# 01_fpga.net
KiCad netlist of a schematic drawn in Altium Designer
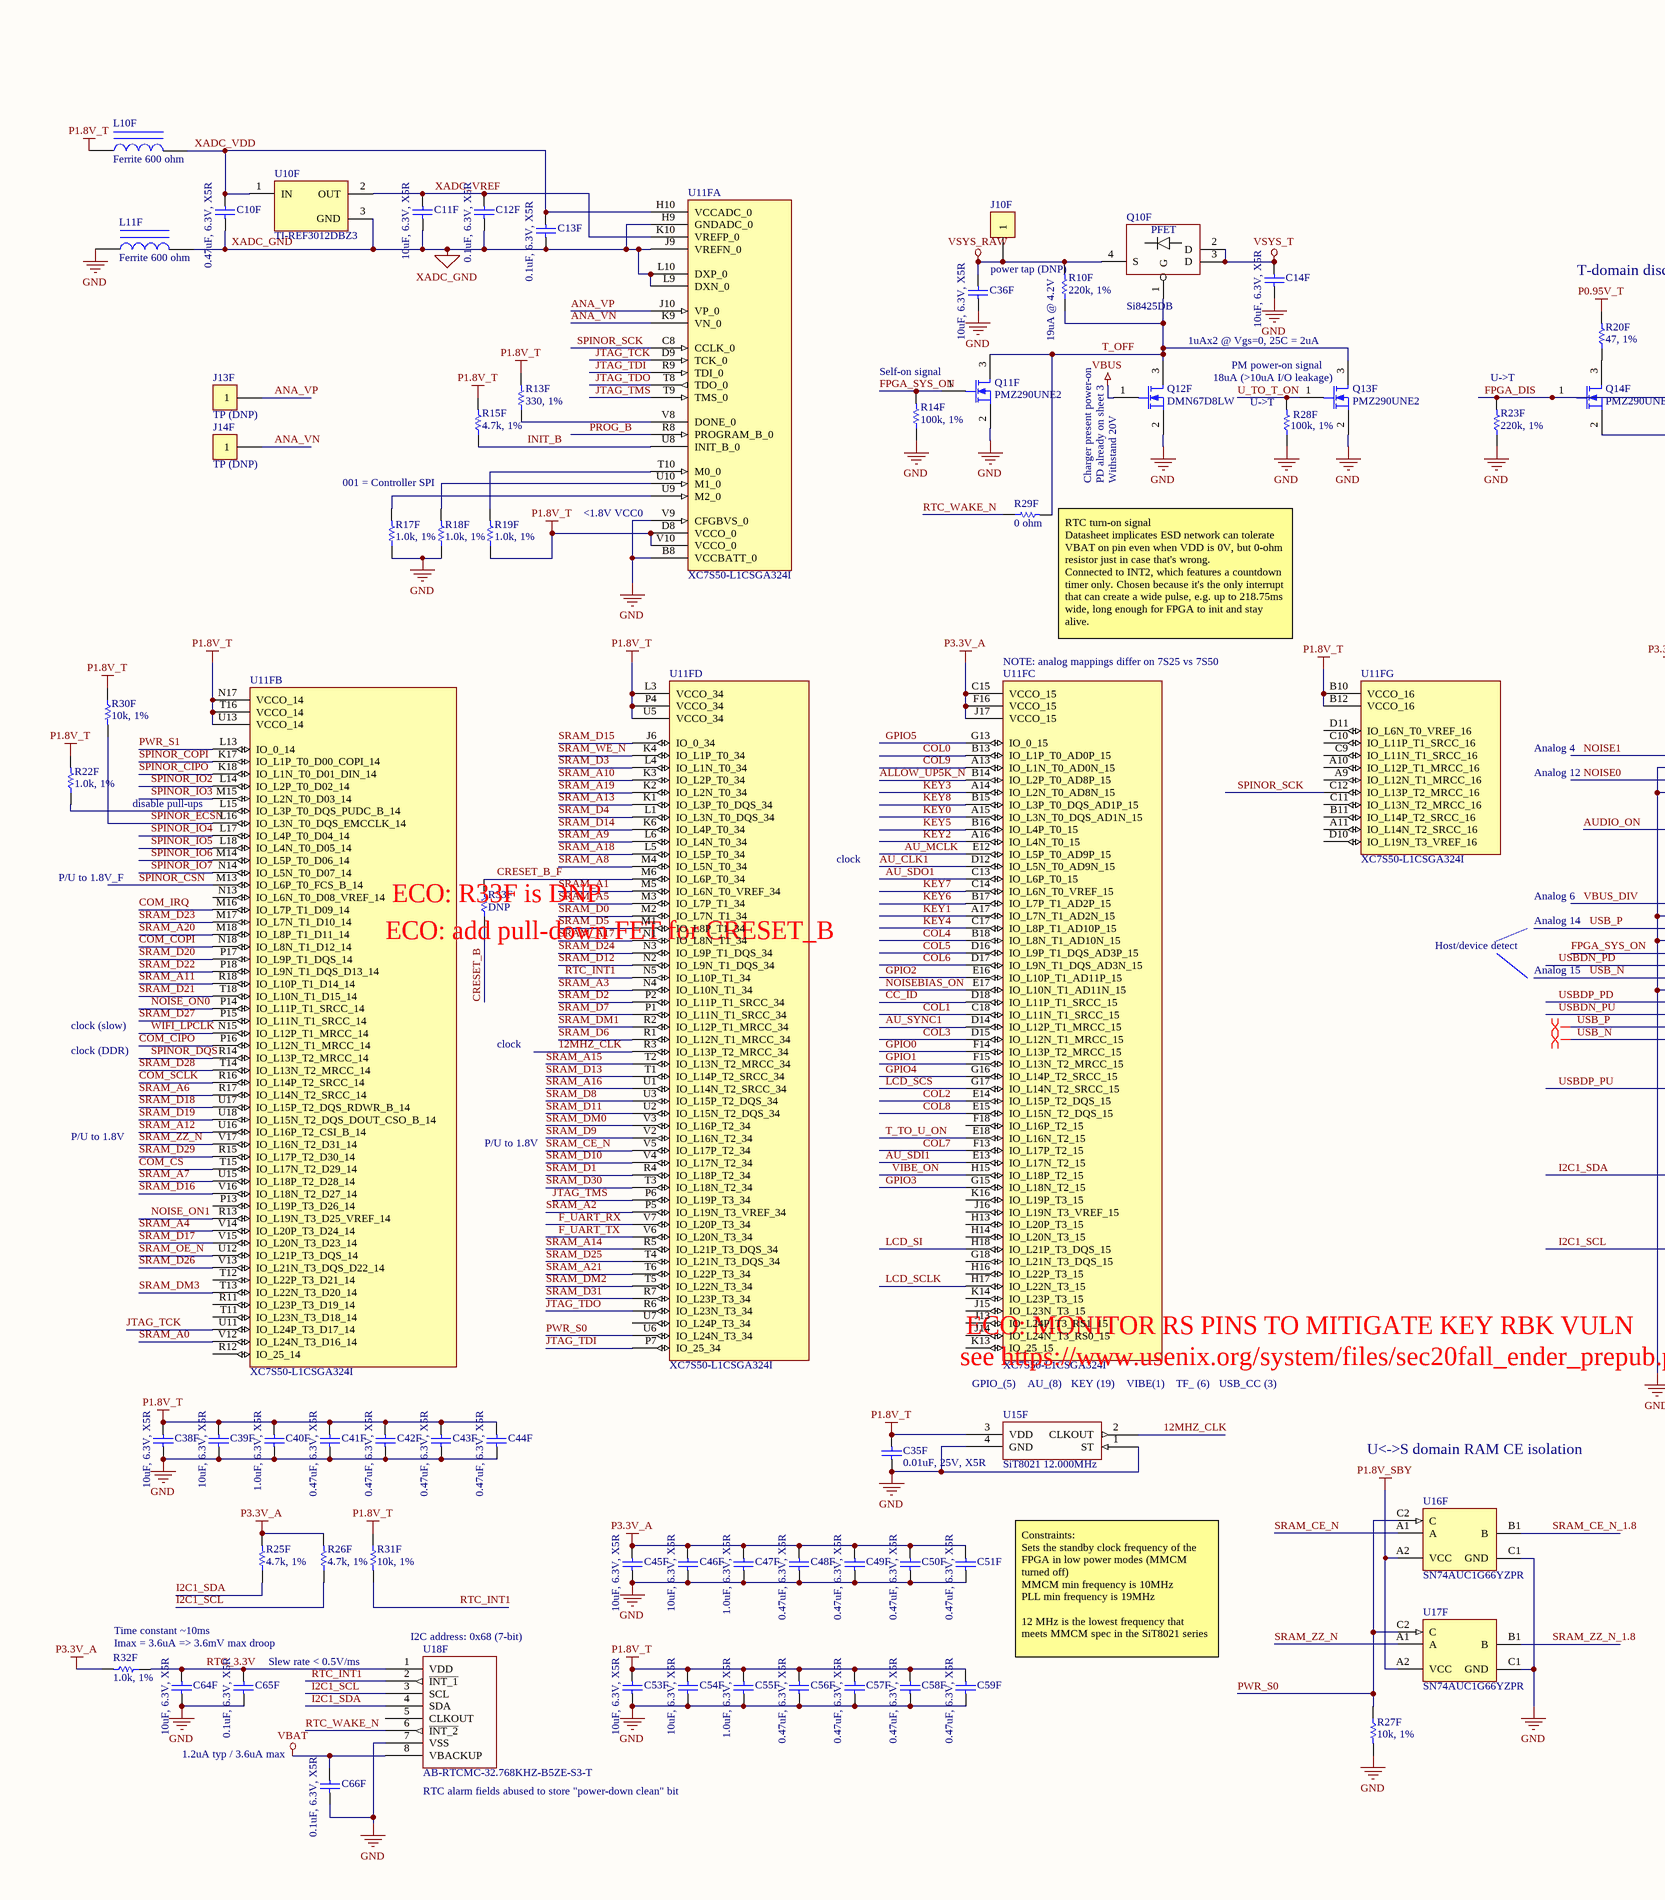
[diagram p0: 01_fpga.SchDoc, left]
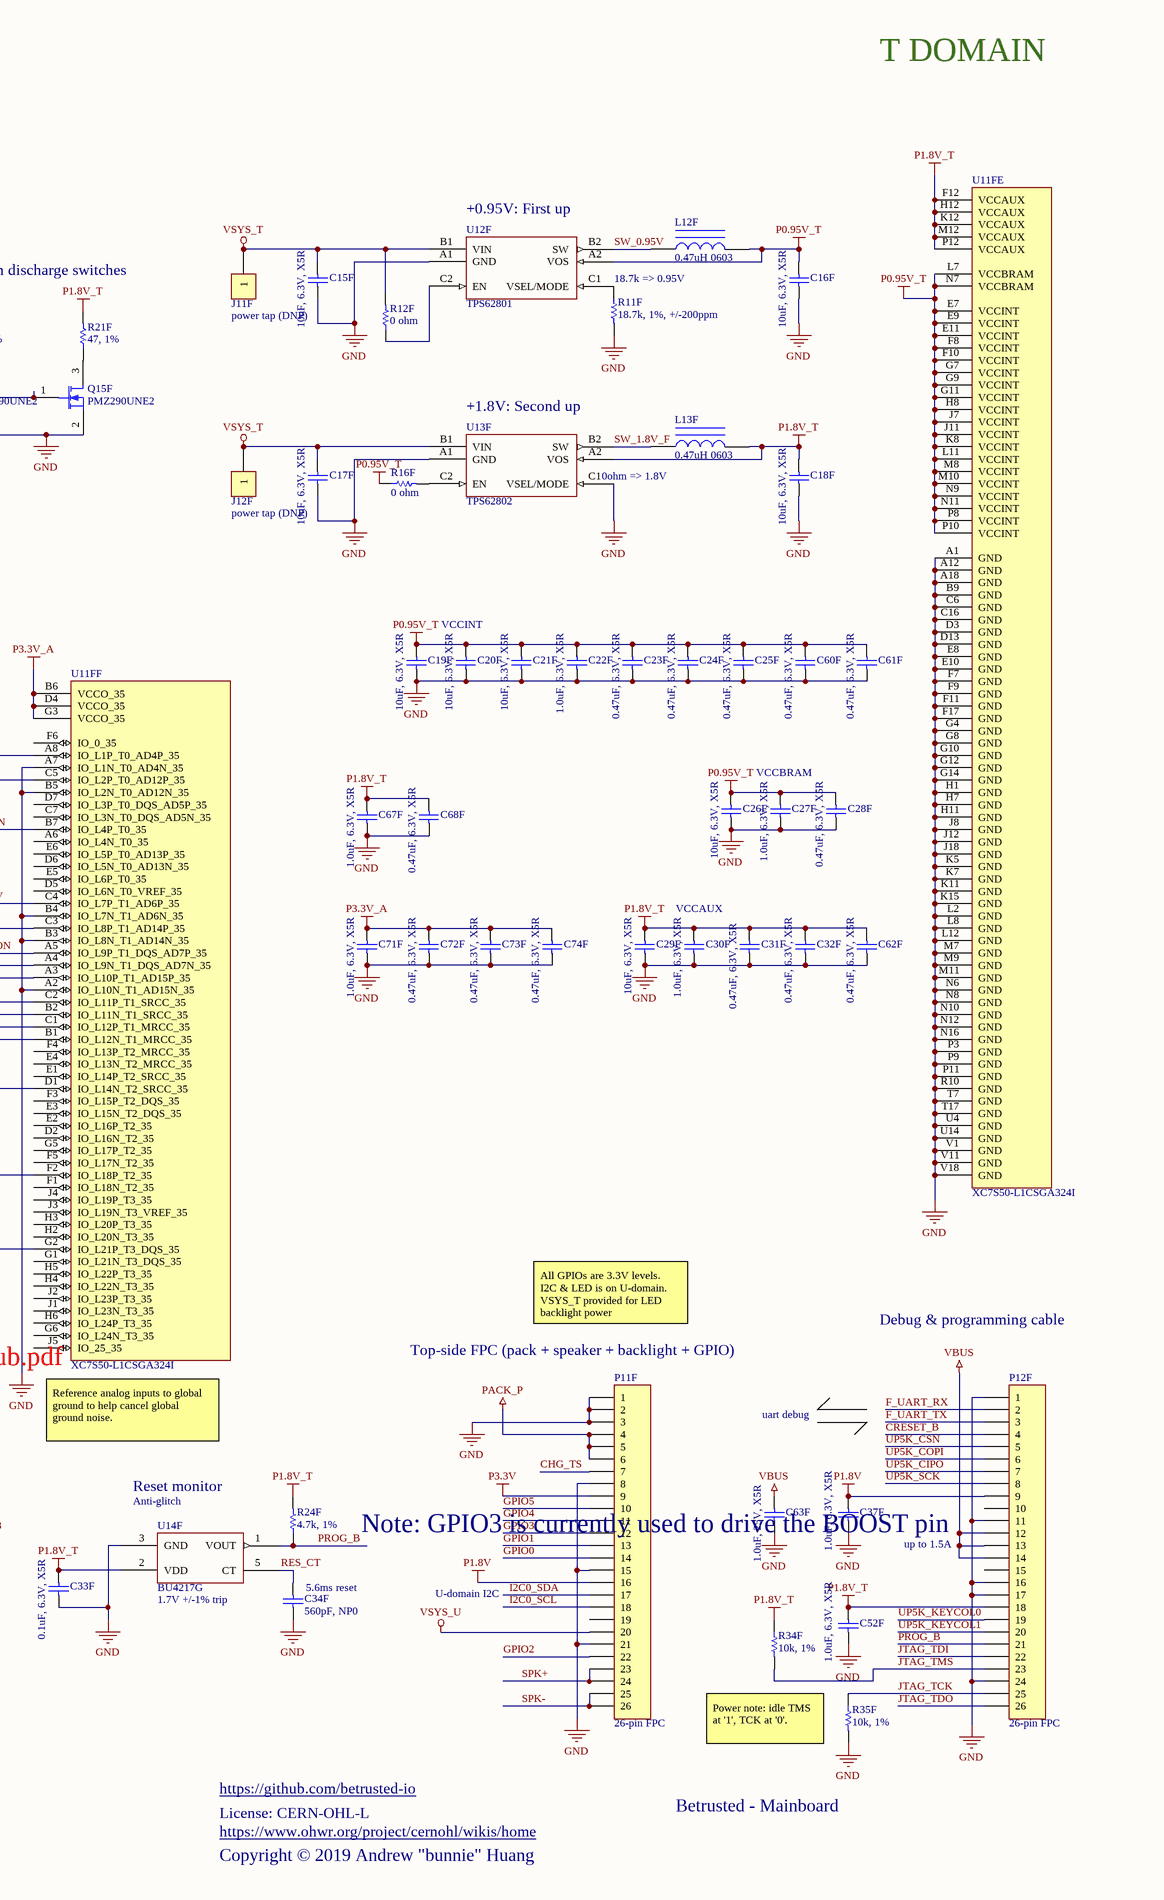
[diagram p1: 01_fpga.SchDoc, right]

(export (version "E")
  (design (tool "Eeschema 10.0.6"))
  (components
    (comp (ref "C10F")
      (value "0.47uF, 6.3V, X5R")
      (footprint "B_CAP0201")
      (description "Capacitor (Semiconductor SIM Model)")
      (fields (field (name "MPN") "CL03A474KQ3NNNH"))
      (libsource (lib "Miscellaneous Devices") (part "Cap Semi"))
    )
    (comp (ref "C11F")
      (value "10uF, 6.3V, X5R")
      (footprint "B_CAP0603")
      (description "Capacitor (Semiconductor SIM Model)")
      (fields (field (name "MPN") "CL10A106MQ8NNNC"))
      (libsource (lib "Miscellaneous Devices") (part "Cap Semi"))
    )
    (comp (ref "C12F")
      (value "0.1uF, 6.3V, X5R")
      (footprint "B_CAP0201")
      (description "Capacitor (Semiconductor SIM Model)")
      (fields (field (name "MPN") "CL03A104KQ3NNNC"))
      (libsource (lib "Miscellaneous Devices") (part "Cap Semi"))
    )
    (comp (ref "C13F")
      (value "0.1uF, 6.3V, X5R")
      (footprint "B_CAP0201")
      (description "Capacitor (Semiconductor SIM Model)")
      (fields (field (name "MPN") "CL03A104KQ3NNNC"))
      (libsource (lib "Miscellaneous Devices") (part "Cap Semi"))
    )
    (comp (ref "C14F")
      (value "10uF, 6.3V, X5R")
      (footprint "B_CAP0603")
      (description "Capacitor (Semiconductor SIM Model)")
      (fields (field (name "MPN") "CL10A106MQ8NNNC"))
      (libsource (lib "Miscellaneous Devices") (part "Cap Semi"))
    )
    (comp (ref "C15F")
      (value "10uF, 6.3V, X5R")
      (footprint "B_CAP0603")
      (description "Capacitor (Semiconductor SIM Model)")
      (fields (field (name "MPN") "CL10A106MQ8NNNC"))
      (libsource (lib "Miscellaneous Devices") (part "Cap Semi"))
    )
    (comp (ref "C16F")
      (value "10uF, 6.3V, X5R")
      (footprint "B_CAP0603")
      (description "Capacitor (Semiconductor SIM Model)")
      (fields (field (name "MPN") "CL10A106MQ8NNNC"))
      (libsource (lib "Miscellaneous Devices") (part "Cap Semi"))
    )
    (comp (ref "C17F")
      (value "10uF, 6.3V, X5R")
      (footprint "B_CAP0603")
      (description "Capacitor (Semiconductor SIM Model)")
      (fields (field (name "MPN") "CL10A106MQ8NNNC"))
      (libsource (lib "Miscellaneous Devices") (part "Cap Semi"))
    )
    (comp (ref "C18F")
      (value "10uF, 6.3V, X5R")
      (footprint "B_CAP0603")
      (description "Capacitor (Semiconductor SIM Model)")
      (fields (field (name "MPN") "CL10A106MQ8NNNC"))
      (libsource (lib "Miscellaneous Devices") (part "Cap Semi"))
    )
    (comp (ref "C19F")
      (value "10uF, 6.3V, X5R")
      (footprint "B_CAP0603")
      (description "Capacitor (Semiconductor SIM Model)")
      (fields (field (name "MPN") "CL10A106MQ8NNNC"))
      (libsource (lib "Miscellaneous Devices") (part "Cap Semi"))
    )
    (comp (ref "C20F")
      (value "10uF, 6.3V, X5R")
      (footprint "B_CAP0603")
      (description "Capacitor (Semiconductor SIM Model)")
      (fields (field (name "MPN") "CL10A106MQ8NNNC"))
      (libsource (lib "Miscellaneous Devices") (part "Cap Semi"))
    )
    (comp (ref "C21F")
      (value "10uF, 6.3V, X5R")
      (footprint "B_CAP0603")
      (description "Capacitor (Semiconductor SIM Model)")
      (fields (field (name "MPN") "CL10A106MQ8NNNC"))
      (libsource (lib "Miscellaneous Devices") (part "Cap Semi"))
    )
    (comp (ref "C22F")
      (value "1.0uF, 6.3V, X5R")
      (footprint "B_CAP0201")
      (description "Capacitor (Semiconductor SIM Model)")
      (fields (field (name "MPN") "GRM033R60J105MEA2D"))
      (libsource (lib "Miscellaneous Devices") (part "Cap Semi"))
    )
    (comp (ref "C23F")
      (value "0.47uF, 6.3V, X5R")
      (footprint "B_CAP0201")
      (description "Capacitor (Semiconductor SIM Model)")
      (fields (field (name "MPN") "CL03A474KQ3NNNH"))
      (libsource (lib "Miscellaneous Devices") (part "Cap Semi"))
    )
    (comp (ref "C24F")
      (value "0.47uF, 6.3V, X5R")
      (footprint "B_CAP0201")
      (description "Capacitor (Semiconductor SIM Model)")
      (fields (field (name "MPN") "CL03A474KQ3NNNH"))
      (libsource (lib "Miscellaneous Devices") (part "Cap Semi"))
    )
    (comp (ref "C25F")
      (value "0.47uF, 6.3V, X5R")
      (footprint "B_CAP0201")
      (description "Capacitor (Semiconductor SIM Model)")
      (fields (field (name "MPN") "CL03A474KQ3NNNH"))
      (libsource (lib "Miscellaneous Devices") (part "Cap Semi"))
    )
    (comp (ref "C26F")
      (value "10uF, 6.3V, X5R")
      (footprint "B_CAP0603")
      (description "Capacitor (Semiconductor SIM Model)")
      (fields (field (name "MPN") "CL10A106MQ8NNNC"))
      (libsource (lib "Miscellaneous Devices") (part "Cap Semi"))
    )
    (comp (ref "C27F")
      (value "1.0uF, 6.3V, X5R")
      (footprint "B_CAP0201")
      (description "Capacitor (Semiconductor SIM Model)")
      (fields (field (name "MPN") "GRM033R60J105MEA2D"))
      (libsource (lib "Miscellaneous Devices") (part "Cap Semi"))
    )
    (comp (ref "C28F")
      (value "0.47uF, 6.3V, X5R")
      (footprint "B_CAP0201")
      (description "Capacitor (Semiconductor SIM Model)")
      (fields (field (name "MPN") "CL03A474KQ3NNNH"))
      (libsource (lib "Miscellaneous Devices") (part "Cap Semi"))
    )
    (comp (ref "C29F")
      (value "10uF, 6.3V, X5R")
      (footprint "B_CAP0603")
      (description "Capacitor (Semiconductor SIM Model)")
      (fields (field (name "MPN") "CL10A106MQ8NNNC"))
      (libsource (lib "Miscellaneous Devices") (part "Cap Semi"))
    )
    (comp (ref "C30F")
      (value "1.0uF, 6.3V, X5R")
      (footprint "B_CAP0201")
      (description "Capacitor (Semiconductor SIM Model)")
      (fields (field (name "MPN") "GRM033R60J105MEA2D"))
      (libsource (lib "Miscellaneous Devices") (part "Cap Semi"))
    )
    (comp (ref "C31F")
      (value "0.47uF, 6.3V, X5R")
      (footprint "B_CAP0201")
      (description "Capacitor (Semiconductor SIM Model)")
      (fields (field (name "MPN") "CL03A474KQ3NNNH"))
      (libsource (lib "Miscellaneous Devices") (part "Cap Semi"))
    )
    (comp (ref "C32F")
      (value "0.47uF, 6.3V, X5R")
      (footprint "B_CAP0201")
      (description "Capacitor (Semiconductor SIM Model)")
      (fields (field (name "MPN") "CL03A474KQ3NNNH"))
      (libsource (lib "Miscellaneous Devices") (part "Cap Semi"))
    )
    (comp (ref "C33F")
      (value "0.1uF, 6.3V, X5R")
      (footprint "B_CAP0201")
      (description "Capacitor (Semiconductor SIM Model)")
      (fields (field (name "MPN") "CL03A104KQ3NNNC"))
      (libsource (lib "Miscellaneous Devices") (part "Cap Semi"))
    )
    (comp (ref "C34F")
      (value "560pF, NP0")
      (footprint "B_RES0201")
      (description "Capacitor (Semiconductor SIM Model)")
      (fields (field (name "MPN") "GRM0335C1E561JA01D"))
      (libsource (lib "Miscellaneous Devices") (part "Cap Semi"))
    )
    (comp (ref "C35F")
      (value "0.01uF, 25V, X5R")
      (footprint "B_RES0201")
      (description "Capacitor (Semiconductor SIM Model)")
      (fields (field (name "MPN") "GRM033R61E103KA12D"))
      (libsource (lib "Miscellaneous Devices") (part "Cap Semi"))
    )
    (comp (ref "C36F")
      (value "10uF, 6.3V, X5R")
      (footprint "B_CAP0603")
      (description "Capacitor (Semiconductor SIM Model)")
      (fields (field (name "MPN") "CL10A106MQ8NNNC"))
      (libsource (lib "Miscellaneous Devices") (part "Cap Semi"))
    )
    (comp (ref "C37F")
      (value "1.0uF, 6.3V, X5R")
      (footprint "B_CAP0201")
      (description "Capacitor (Semiconductor SIM Model)")
      (fields (field (name "MPN") "GRM033R60J105MEA2D"))
      (libsource (lib "Miscellaneous Devices") (part "Cap Semi"))
    )
    (comp (ref "C38F")
      (value "10uF, 6.3V, X5R")
      (footprint "B_CAP0603")
      (description "Capacitor (Semiconductor SIM Model)")
      (fields (field (name "MPN") "CL10A106MQ8NNNC"))
      (libsource (lib "Miscellaneous Devices") (part "Cap Semi"))
    )
    (comp (ref "C39F")
      (value "10uF, 6.3V, X5R")
      (footprint "B_CAP0603")
      (description "Capacitor (Semiconductor SIM Model)")
      (fields (field (name "MPN") "CL10A106MQ8NNNC"))
      (libsource (lib "Miscellaneous Devices") (part "Cap Semi"))
    )
    (comp (ref "C40F")
      (value "1.0uF, 6.3V, X5R")
      (footprint "B_CAP0201")
      (description "Capacitor (Semiconductor SIM Model)")
      (fields (field (name "MPN") "GRM033R60J105MEA2D"))
      (libsource (lib "Miscellaneous Devices") (part "Cap Semi"))
    )
    (comp (ref "C41F")
      (value "0.47uF, 6.3V, X5R")
      (footprint "B_CAP0201")
      (description "Capacitor (Semiconductor SIM Model)")
      (fields (field (name "MPN") "CL03A474KQ3NNNH"))
      (libsource (lib "Miscellaneous Devices") (part "Cap Semi"))
    )
    (comp (ref "C42F")
      (value "0.47uF, 6.3V, X5R")
      (footprint "B_CAP0201")
      (description "Capacitor (Semiconductor SIM Model)")
      (fields (field (name "MPN") "CL03A474KQ3NNNH"))
      (libsource (lib "Miscellaneous Devices") (part "Cap Semi"))
    )
    (comp (ref "C43F")
      (value "0.47uF, 6.3V, X5R")
      (footprint "B_CAP0201")
      (description "Capacitor (Semiconductor SIM Model)")
      (fields (field (name "MPN") "CL03A474KQ3NNNH"))
      (libsource (lib "Miscellaneous Devices") (part "Cap Semi"))
    )
    (comp (ref "C44F")
      (value "0.47uF, 6.3V, X5R")
      (footprint "B_CAP0201")
      (description "Capacitor (Semiconductor SIM Model)")
      (fields (field (name "MPN") "CL03A474KQ3NNNH"))
      (libsource (lib "Miscellaneous Devices") (part "Cap Semi"))
    )
    (comp (ref "C45F")
      (value "10uF, 6.3V, X5R")
      (footprint "B_CAP0603")
      (description "Capacitor (Semiconductor SIM Model)")
      (fields (field (name "MPN") "CL10A106MQ8NNNC"))
      (libsource (lib "Miscellaneous Devices") (part "Cap Semi"))
    )
    (comp (ref "C46F")
      (value "10uF, 6.3V, X5R")
      (footprint "B_CAP0603")
      (description "Capacitor (Semiconductor SIM Model)")
      (fields (field (name "MPN") "CL10A106MQ8NNNC"))
      (libsource (lib "Miscellaneous Devices") (part "Cap Semi"))
    )
    (comp (ref "C47F")
      (value "1.0uF, 6.3V, X5R")
      (footprint "B_CAP0201")
      (description "Capacitor (Semiconductor SIM Model)")
      (fields (field (name "MPN") "GRM033R60J105MEA2D"))
      (libsource (lib "Miscellaneous Devices") (part "Cap Semi"))
    )
    (comp (ref "C48F")
      (value "0.47uF, 6.3V, X5R")
      (footprint "B_CAP0201")
      (description "Capacitor (Semiconductor SIM Model)")
      (fields (field (name "MPN") "CL03A474KQ3NNNH"))
      (libsource (lib "Miscellaneous Devices") (part "Cap Semi"))
    )
    (comp (ref "C49F")
      (value "0.47uF, 6.3V, X5R")
      (footprint "B_CAP0201")
      (description "Capacitor (Semiconductor SIM Model)")
      (fields (field (name "MPN") "CL03A474KQ3NNNH"))
      (libsource (lib "Miscellaneous Devices") (part "Cap Semi"))
    )
    (comp (ref "C50F")
      (value "0.47uF, 6.3V, X5R")
      (footprint "B_CAP0201")
      (description "Capacitor (Semiconductor SIM Model)")
      (fields (field (name "MPN") "CL03A474KQ3NNNH"))
      (libsource (lib "Miscellaneous Devices") (part "Cap Semi"))
    )
    (comp (ref "C51F")
      (value "0.47uF, 6.3V, X5R")
      (footprint "B_CAP0201")
      (description "Capacitor (Semiconductor SIM Model)")
      (fields (field (name "MPN") "CL03A474KQ3NNNH"))
      (libsource (lib "Miscellaneous Devices") (part "Cap Semi"))
    )
    (comp (ref "C52F")
      (value "1.0uF, 6.3V, X5R")
      (footprint "B_CAP0201")
      (description "Capacitor (Semiconductor SIM Model)")
      (fields (field (name "MPN") "GRM033R60J105MEA2D"))
      (libsource (lib "Miscellaneous Devices") (part "Cap Semi"))
    )
    (comp (ref "C53F")
      (value "10uF, 6.3V, X5R")
      (footprint "B_CAP0603")
      (description "Capacitor (Semiconductor SIM Model)")
      (fields (field (name "MPN") "CL10A106MQ8NNNC"))
      (libsource (lib "Miscellaneous Devices") (part "Cap Semi"))
    )
    (comp (ref "C54F")
      (value "10uF, 6.3V, X5R")
      (footprint "B_CAP0603")
      (description "Capacitor (Semiconductor SIM Model)")
      (fields (field (name "MPN") "CL10A106MQ8NNNC"))
      (libsource (lib "Miscellaneous Devices") (part "Cap Semi"))
    )
    (comp (ref "C55F")
      (value "1.0uF, 6.3V, X5R")
      (footprint "B_CAP0201")
      (description "Capacitor (Semiconductor SIM Model)")
      (fields (field (name "MPN") "GRM033R60J105MEA2D"))
      (libsource (lib "Miscellaneous Devices") (part "Cap Semi"))
    )
    (comp (ref "C56F")
      (value "0.47uF, 6.3V, X5R")
      (footprint "B_CAP0201")
      (description "Capacitor (Semiconductor SIM Model)")
      (fields (field (name "MPN") "CL03A474KQ3NNNH"))
      (libsource (lib "Miscellaneous Devices") (part "Cap Semi"))
    )
    (comp (ref "C57F")
      (value "0.47uF, 6.3V, X5R")
      (footprint "B_CAP0201")
      (description "Capacitor (Semiconductor SIM Model)")
      (fields (field (name "MPN") "CL03A474KQ3NNNH"))
      (libsource (lib "Miscellaneous Devices") (part "Cap Semi"))
    )
    (comp (ref "C58F")
      (value "0.47uF, 6.3V, X5R")
      (footprint "B_CAP0201")
      (description "Capacitor (Semiconductor SIM Model)")
      (fields (field (name "MPN") "CL03A474KQ3NNNH"))
      (libsource (lib "Miscellaneous Devices") (part "Cap Semi"))
    )
    (comp (ref "C59F")
      (value "0.47uF, 6.3V, X5R")
      (footprint "B_CAP0201")
      (description "Capacitor (Semiconductor SIM Model)")
      (fields (field (name "MPN") "CL03A474KQ3NNNH"))
      (libsource (lib "Miscellaneous Devices") (part "Cap Semi"))
    )
    (comp (ref "C60F")
      (value "0.47uF, 6.3V, X5R")
      (footprint "B_CAP0201")
      (description "Capacitor (Semiconductor SIM Model)")
      (fields (field (name "MPN") "CL03A474KQ3NNNH"))
      (libsource (lib "Miscellaneous Devices") (part "Cap Semi"))
    )
    (comp (ref "C61F")
      (value "0.47uF, 6.3V, X5R")
      (footprint "B_CAP0201")
      (description "Capacitor (Semiconductor SIM Model)")
      (fields (field (name "MPN") "CL03A474KQ3NNNH"))
      (libsource (lib "Miscellaneous Devices") (part "Cap Semi"))
    )
    (comp (ref "C62F")
      (value "0.47uF, 6.3V, X5R")
      (footprint "B_CAP0201")
      (description "Capacitor (Semiconductor SIM Model)")
      (fields (field (name "MPN") "CL03A474KQ3NNNH"))
      (libsource (lib "Miscellaneous Devices") (part "Cap Semi"))
    )
    (comp (ref "C63F")
      (value "1.0uF, 25V, X5R")
      (footprint "B_CAP0603")
      (description "Capacitor (Semiconductor SIM Model)")
      (fields (field (name "MPN") "CL10A105KA8NNNC"))
      (libsource (lib "Miscellaneous Devices") (part "Cap Semi"))
    )
    (comp (ref "C64F")
      (value "10uF, 6.3V, X5R")
      (footprint "B_CAP0603")
      (description "Capacitor (Semiconductor SIM Model)")
      (fields (field (name "MPN") "CL10A106MQ8NNNC"))
      (libsource (lib "Miscellaneous Devices") (part "Cap Semi"))
    )
    (comp (ref "C65F")
      (value "0.1uF, 6.3V, X5R")
      (footprint "B_CAP0201")
      (description "Capacitor (Semiconductor SIM Model)")
      (fields (field (name "MPN") "CL03A104KQ3NNNC"))
      (libsource (lib "Miscellaneous Devices") (part "Cap Semi"))
    )
    (comp (ref "C66F")
      (value "0.1uF, 6.3V, X5R")
      (footprint "B_CAP0201")
      (description "Capacitor (Semiconductor SIM Model)")
      (fields (field (name "MPN") "CL03A104KQ3NNNC"))
      (libsource (lib "Miscellaneous Devices") (part "Cap Semi"))
    )
    (comp (ref "C67F")
      (value "1.0uF, 6.3V, X5R")
      (footprint "B_CAP0201")
      (description "Capacitor (Semiconductor SIM Model)")
      (fields (field (name "MPN") "GRM033R60J105MEA2D"))
      (libsource (lib "Miscellaneous Devices") (part "Cap Semi"))
    )
    (comp (ref "C68F")
      (value "0.47uF, 6.3V, X5R")
      (footprint "B_CAP0201")
      (description "Capacitor (Semiconductor SIM Model)")
      (fields (field (name "MPN") "CL03A474KQ3NNNH"))
      (libsource (lib "Miscellaneous Devices") (part "Cap Semi"))
    )
    (comp (ref "C71F")
      (value "1.0uF, 6.3V, X5R")
      (footprint "B_CAP0201")
      (description "Capacitor (Semiconductor SIM Model)")
      (fields (field (name "MPN") "GRM033R60J105MEA2D"))
      (libsource (lib "Miscellaneous Devices") (part "Cap Semi"))
    )
    (comp (ref "C72F")
      (value "0.47uF, 6.3V, X5R")
      (footprint "B_CAP0201")
      (description "Capacitor (Semiconductor SIM Model)")
      (fields (field (name "MPN") "CL03A474KQ3NNNH"))
      (libsource (lib "Miscellaneous Devices") (part "Cap Semi"))
    )
    (comp (ref "C73F")
      (value "0.47uF, 6.3V, X5R")
      (footprint "B_CAP0201")
      (description "Capacitor (Semiconductor SIM Model)")
      (fields (field (name "MPN") "CL03A474KQ3NNNH"))
      (libsource (lib "Miscellaneous Devices") (part "Cap Semi"))
    )
    (comp (ref "C74F")
      (value "0.47uF, 6.3V, X5R")
      (footprint "B_CAP0201")
      (description "Capacitor (Semiconductor SIM Model)")
      (fields (field (name "MPN") "CL03A474KQ3NNNH"))
      (libsource (lib "Miscellaneous Devices") (part "Cap Semi"))
    )
    (comp (ref "J10F")
      (value "power tap (DNP)")
      (footprint "RESTAP-0603")
      (description "Connector")
      (fields (field (name "MPN") "DNP"))
      (libsource (lib "*") (part "CON1"))
    )
    (comp (ref "J11F")
      (value "power tap (DNP)")
      (footprint "RESTAP-0603")
      (description "Connector")
      (fields (field (name "MPN") "DNP"))
      (libsource (lib "") (part "CON1_1"))
    )
    (comp (ref "J12F")
      (value "power tap (DNP)")
      (footprint "RESTAP-0603")
      (description "Connector")
      (fields (field (name "MPN") "DNP"))
      (libsource (lib "") (part "CON1_1"))
    )
    (comp (ref "J13F")
      (value "TP (DNP)")
      (footprint "TP_0.4x0.4_SMT")
      (description "Connector")
      (fields (field (name "MPN") "DNP"))
      (libsource (lib "") (part "CON1_2"))
    )
    (comp (ref "J14F")
      (value "TP (DNP)")
      (footprint "TP_0.4x0.4_SMT")
      (description "Connector")
      (fields (field (name "MPN") "DNP"))
      (libsource (lib "") (part "CON1_2"))
    )
    (comp (ref "L10F")
      (value "Ferrite 600 ohm")
      (footprint "B_IND0603")
      (description "Magnetic-Core Inductor")
      (fields (field (name "MPN") "BLM18AG601SN1D"))
      (libsource (lib "Miscellaneous Devices") (part "Inductor Iron"))
    )
    (comp (ref "L11F")
      (value "Ferrite 600 ohm")
      (footprint "B_IND0603")
      (description "Magnetic-Core Inductor")
      (fields (field (name "MPN") "BLM18AG601SN1D"))
      (libsource (lib "Miscellaneous Devices") (part "Inductor Iron"))
    )
    (comp (ref "L12F")
      (value "0.47uH 0603")
      (footprint "B_IND0603")
      (description "Magnetic-Core Inductor")
      (fields (field (name "MPN") "TFM160808ALC-R47MTAA"))
      (libsource (lib "Miscellaneous Devices") (part "Inductor Iron"))
    )
    (comp (ref "L13F")
      (value "0.47uH 0603")
      (footprint "B_IND0603")
      (description "Magnetic-Core Inductor")
      (fields (field (name "MPN") "TFM160808ALC-R47MTAA"))
      (libsource (lib "Miscellaneous Devices") (part "Inductor Iron"))
    )
    (comp (ref "P11F")
      (value "26-pin FPC")
      (footprint "HRS_FH34SRJ-26S-0.5SH(50)")
      (description "26 Pin FPC header")
      (fields (field (name "MPN") "FH34SRJ-26S-0.5SH(99)"))
      (libsource (lib "commonsch-new") (part "FPC-26"))
    )
    (comp (ref "P12F")
      (value "26-pin FPC")
      (footprint "HRS_FH34SRJ-26S-0.5SH(50)")
      (description "26 Pin FPC header")
      (fields (field (name "MPN") "FH34SRJ-26S-0.5SH(99)"))
      (libsource (lib "commonsch-new") (part "FPC-26"))
    )
    (comp (ref "Q10F")
      (value "Si8425DB")
      (footprint "VISHAY_MICRO_FOOT_4_BUMP")
      (description "P-channel 20V 6.2A 27mOhm @ -2.5V")
      (fields (field (name "MPN") "SI8457DB-T1-E1"))
      (libsource (lib "temp-to-merge") (part "Si8425DB"))
    )
    (comp (ref "Q11F")
      (value "PMZ290UNE2")
      (footprint "SOT883")
      (description "N-Channel MOSFET")
      (fields (field (name "PUBLISHER") "Altium Limited"))
      (libsource (lib "Miscellaneous Devices") (part "MOSFET-N"))
    )
    (comp (ref "Q12F")
      (value "DMN67D8LW")
      (footprint "SOT323-3AN")
      (description "N-Channel MOSFET")
      (fields (field (name "PUBLISHER") "Altium Limited"))
      (libsource (lib "Miscellaneous Devices") (part "MOSFET-N"))
    )
    (comp (ref "Q13F")
      (value "PMZ290UNE2")
      (footprint "SOT883")
      (description "N-Channel MOSFET")
      (fields (field (name "PUBLISHER") "Altium Limited"))
      (libsource (lib "Miscellaneous Devices") (part "MOSFET-N"))
    )
    (comp (ref "Q14F")
      (value "PMZ290UNE2")
      (footprint "SOT883")
      (description "N-Channel MOSFET")
      (fields (field (name "PUBLISHER") "Altium Limited"))
      (libsource (lib "Miscellaneous Devices") (part "MOSFET-N"))
    )
    (comp (ref "Q15F")
      (value "PMZ290UNE2")
      (footprint "SOT883")
      (description "N-Channel MOSFET")
      (fields (field (name "PUBLISHER") "Altium Limited"))
      (libsource (lib "Miscellaneous Devices") (part "MOSFET-N"))
    )
    (comp (ref "R10F")
      (value "220k, 1%")
      (footprint "B_RES0201")
      (description "Resistor")
      (fields (field (name "MPN") "ANY"))
      (libsource (lib "Miscellaneous Devices") (part "Res1"))
    )
    (comp (ref "R11F")
      (value "18.7k, 1%, +/-200ppm")
      (footprint "B_RES0402")
      (description "Resistor")
      (fields (field (name "MPN") "RC0402FR-0718K7L"))
      (libsource (lib "Miscellaneous Devices") (part "Res1"))
    )
    (comp (ref "R12F")
      (value "0 ohm")
      (footprint "B_RES0201")
      (description "Resistor")
      (fields (field (name "MPN") "ANY"))
      (libsource (lib "Miscellaneous Devices") (part "Res1"))
    )
    (comp (ref "R13F")
      (value "330, 1%")
      (footprint "B_RES0201")
      (description "Resistor")
      (fields (field (name "MPN") "ANY"))
      (libsource (lib "Miscellaneous Devices") (part "Res1"))
    )
    (comp (ref "R14F")
      (value "100k, 1%")
      (footprint "B_RES0201")
      (description "Resistor")
      (fields (field (name "MPN") "ANY"))
      (libsource (lib "Miscellaneous Devices") (part "Res1"))
    )
    (comp (ref "R15F")
      (value "4.7k, 1%")
      (footprint "B_RES0201")
      (description "Resistor")
      (fields (field (name "MPN") "ANY"))
      (libsource (lib "Miscellaneous Devices") (part "Res1"))
    )
    (comp (ref "R16F")
      (value "0 ohm")
      (footprint "B_RES0201")
      (description "Resistor")
      (fields (field (name "MPN") "ANY"))
      (libsource (lib "Miscellaneous Devices") (part "Res1"))
    )
    (comp (ref "R17F")
      (value "1.0k, 1%")
      (footprint "B_RES0201")
      (description "Resistor")
      (fields (field (name "MPN") "ANY"))
      (libsource (lib "Miscellaneous Devices") (part "Res1"))
    )
    (comp (ref "R18F")
      (value "1.0k, 1%")
      (footprint "B_RES0201")
      (description "Resistor")
      (fields (field (name "MPN") "ANY"))
      (libsource (lib "Miscellaneous Devices") (part "Res1"))
    )
    (comp (ref "R19F")
      (value "1.0k, 1%")
      (footprint "B_RES0201")
      (description "Resistor")
      (fields (field (name "MPN") "ANY"))
      (libsource (lib "Miscellaneous Devices") (part "Res1"))
    )
    (comp (ref "R20F")
      (value "47, 1%")
      (footprint "B_RES0402")
      (description "Resistor")
      (fields (field (name "MPN") "ANY"))
      (libsource (lib "Miscellaneous Devices") (part "Res1"))
    )
    (comp (ref "R21F")
      (value "47, 1%")
      (footprint "B_RES0402")
      (description "Resistor")
      (fields (field (name "MPN") "ANY"))
      (libsource (lib "Miscellaneous Devices") (part "Res1"))
    )
    (comp (ref "R22F")
      (value "1.0k, 1%")
      (footprint "B_RES0201")
      (description "Resistor")
      (fields (field (name "MPN") "ANY"))
      (libsource (lib "Miscellaneous Devices") (part "Res1"))
    )
    (comp (ref "R23F")
      (value "220k, 1%")
      (footprint "B_RES0201")
      (description "Resistor")
      (fields (field (name "MPN") "ANY"))
      (libsource (lib "Miscellaneous Devices") (part "Res1"))
    )
    (comp (ref "R24F")
      (value "4.7k, 1%")
      (footprint "B_RES0201")
      (description "Resistor")
      (fields (field (name "MPN") "ANY"))
      (libsource (lib "Miscellaneous Devices") (part "Res1"))
    )
    (comp (ref "R25F")
      (value "4.7k, 1%")
      (footprint "B_RES0201")
      (description "Resistor")
      (fields (field (name "MPN") "ANY"))
      (libsource (lib "Miscellaneous Devices") (part "Res1"))
    )
    (comp (ref "R26F")
      (value "4.7k, 1%")
      (footprint "B_RES0201")
      (description "Resistor")
      (fields (field (name "MPN") "ANY"))
      (libsource (lib "Miscellaneous Devices") (part "Res1"))
    )
    (comp (ref "R27F")
      (value "10k, 1%")
      (footprint "B_RES0201")
      (description "Resistor")
      (fields (field (name "MPN") "ANY"))
      (libsource (lib "Miscellaneous Devices") (part "Res1"))
    )
    (comp (ref "R28F")
      (value "100k, 1%")
      (footprint "B_RES0201")
      (description "Resistor")
      (fields (field (name "MPN") "ANY"))
      (libsource (lib "Miscellaneous Devices") (part "Res1"))
    )
    (comp (ref "R29F")
      (value "0 ohm")
      (footprint "B_RES0201")
      (description "Resistor")
      (fields (field (name "MPN") "ANY"))
      (libsource (lib "Miscellaneous Devices") (part "Res1"))
    )
    (comp (ref "R30F")
      (value "10k, 1%")
      (footprint "B_RES0201")
      (description "Resistor")
      (fields (field (name "MPN") "ANY"))
      (libsource (lib "Miscellaneous Devices") (part "Res1"))
    )
    (comp (ref "R31F")
      (value "10k, 1%")
      (footprint "B_RES0201")
      (description "Resistor")
      (fields (field (name "MPN") "ANY"))
      (libsource (lib "Miscellaneous Devices") (part "Res1"))
    )
    (comp (ref "R32F")
      (value "1.0k, 1%")
      (footprint "B_RES0201")
      (description "Resistor")
      (fields (field (name "MPN") "ANY"))
      (libsource (lib "Miscellaneous Devices") (part "Res1"))
    )
    (comp (ref "R33F")
      (value "DNP")
      (footprint "B_RES0201")
      (description "Resistor")
      (fields (field (name "MPN") "ANY"))
      (libsource (lib "Miscellaneous Devices") (part "Res1"))
    )
    (comp (ref "R34F")
      (value "10k, 1%")
      (footprint "B_RES0201")
      (description "Resistor")
      (fields (field (name "MPN") "ANY"))
      (libsource (lib "Miscellaneous Devices") (part "Res1"))
    )
    (comp (ref "R35F")
      (value "10k, 1%")
      (footprint "B_RES0201")
      (description "Resistor")
      (fields (field (name "MPN") "ANY"))
      (libsource (lib "Miscellaneous Devices") (part "Res1"))
    )
    (comp (ref "U10F")
      (value "TI-REF3012DBZ3")
      (footprint "ONSC-SOT-23-3-318-08_V")
      (fields (field (name "MPN") "REF3012AIDBZT"))
      (libsource (lib "TI-REF3012DBZ3") (part "TI-REF3012DBZ3"))
    )
    (comp (ref "U11F")
      (value "XC7S50-L1CSGA324I")
      (footprint "BGA324C80P18X18_1500X1500X150")
      (description "Spartan 7 FPGA in CSGA324 package")
      (libsource (lib "commonsch-new") (part "XC7S50CSGA324"))
    )
    (comp (ref "U12F")
      (value "TPS62801")
      (footprint "BGA6C35P2X3_70X105X40_NSMD")
      (description "Buck regulator, 4MHz, 0.6A, 0.8V-1.55V, low Iq")
      (fields (field (name "MPN") "TPS62801YKAT"))
      (libsource (lib "altium-import") (part "root_0_TPS62801_"))
    )
    (comp (ref "U13F")
      (value "TPS62802")
      (footprint "BGA6C35P2X3_70X105X40_NSMD")
      (description "Buck regulator, 4MHz, 0.6A, 1.8V-3.3V, low Iq")
      (fields (field (name "MPN") "TPS62802YKAR"))
      (libsource (lib "altium-import") (part "root_0_TPS62802_"))
    )
    (comp (ref "U14F")
      (value "BU4217G")
      (footprint "SOT23-5AN")
      (description "Low voltage free delay time setting CMOS voltage detector IC")
      (fields (field (name "MPN") "BU4217G-TR"))
      (libsource (lib "commonsch-new") (part "BU42XXG"))
    )
    (comp (ref "U15F")
      (value "SiT8021 12.000MHz")
      (footprint "SiTIME_CSP")
      (description "1 to 26 MHz micropower oscillator")
      (fields (field (name "MPN") "SIT8021AI-J4-18S-12.000000E"))
      (libsource (lib "altium-import") (part "root_2_SiT8021_"))
    )
    (comp (ref "U16F")
      (value "SN74AUC1G66YZPR")
      (footprint "YZP0005ADAD")
      (description "Single Bilateral Analog Switch, YZP0005ADAD, LARGE T&R")
      (fields
        (field (name "MANUFACTURER") "Texas Instruments")
        (field (name "GENERIC PART NUMBER") "SN74AUC1G66")
      )
      (libsource (lib "Components - 04.06.19 - 14.52") (part "CMP-0859-01029-3"))
    )
    (comp (ref "U17F")
      (value "SN74AUC1G66YZPR")
      (footprint "YZP0005ADAD")
      (description "Single Bilateral Analog Switch, YZP0005ADAD, LARGE T&R")
      (fields
        (field (name "MANUFACTURER") "Texas Instruments")
        (field (name "GENERIC PART NUMBER") "SN74AUC1G66")
      )
      (libsource (lib "Components - 04.06.19 - 14.52") (part "CMP-0859-01029-3"))
    )
    (comp (ref "U18F")
      (value "AB-RTCMC-32.768KHZ-B5ZE-S3-T")
      (footprint "ABRACON_RTCMC_LGA10")
      (description "RTC Module with I2C Bus")
      (libsource (lib "commonsch-new") (part "AB-RTCMC-32.768kHZ-B5ZE-S3"))
    )
  )
  (nets
    (net (code "1") (name "/12MHZ_CLK") (class "Default")
      (node (ref "U11F") (pin "R3") (pinfunction "IO_L13P_T2_MRCC_34_R3") (pintype "bidirectional"))
      (node (ref "U15F") (pin "2") (pinfunction "CLKOUT_2") (pintype "output"))
    )
    (net (code "2") (name "/ALLOW_UP5K_N") (class "Default")
      (node (ref "U11F") (pin "B14") (pinfunction "IO_L2P_T0_AD8P_15_B14") (pintype "bidirectional"))
    )
    (net (code "3") (name "/ANA_VN") (class "Default")
      (node (ref "J14F") (pin "1") (pinfunction "1_1") (pintype "passive"))
      (node (ref "U11F") (pin "K9") (pinfunction "VN_0_K9") (pintype "passive"))
    )
    (net (code "4") (name "/ANA_VP") (class "Default")
      (node (ref "J13F") (pin "1") (pinfunction "1_1") (pintype "passive"))
      (node (ref "U11F") (pin "J10") (pinfunction "VP_0_J10") (pintype "input"))
    )
    (net (code "5") (name "/AUDIO_ON") (class "Default")
      (node (ref "U11F") (pin "B7") (pinfunction "IO_L4P_T0_35_B7") (pintype "bidirectional"))
    )
    (net (code "6") (name "/AU_CLK1") (class "Default")
      (node (ref "U11F") (pin "D12") (pinfunction "IO_L5N_T0_AD9N_15_D12") (pintype "bidirectional"))
    )
    (net (code "7") (name "/AU_MCLK") (class "Default")
      (node (ref "U11F") (pin "E12") (pinfunction "IO_L5P_T0_AD9P_15_E12") (pintype "bidirectional"))
    )
    (net (code "8") (name "/AU_SDI1") (class "Default")
      (node (ref "U11F") (pin "E13") (pinfunction "IO_L17N_T2_15_E13") (pintype "bidirectional"))
    )
    (net (code "9") (name "/AU_SDO1") (class "Default")
      (node (ref "U11F") (pin "C13") (pinfunction "IO_L6P_T0_15_C13") (pintype "bidirectional"))
    )
    (net (code "10") (name "/AU_SYNC1") (class "Default")
      (node (ref "U11F") (pin "D14") (pinfunction "IO_L12P_T1_MRCC_15_D14") (pintype "bidirectional"))
    )
    (net (code "11") (name "/CC_ID") (class "Default")
      (node (ref "U11F") (pin "D18") (pinfunction "IO_L11P_T1_SRCC_15_D18") (pintype "bidirectional"))
    )
    (net (code "12") (name "/CHG_TS") (class "Default")
      (node (ref "P11F") (pin "7") (pinfunction "7_7") (pintype "passive"))
    )
    (net (code "13") (name "/COL0") (class "Default")
      (node (ref "U11F") (pin "B13") (pinfunction "IO_L1P_T0_AD0P_15_B13") (pintype "bidirectional"))
    )
    (net (code "14") (name "/COL1") (class "Default")
      (node (ref "U11F") (pin "C18") (pinfunction "IO_L11N_T1_SRCC_15_C18") (pintype "bidirectional"))
    )
    (net (code "15") (name "/COL2") (class "Default")
      (node (ref "U11F") (pin "E14") (pinfunction "IO_L15P_T2_DQS_15_E14") (pintype "bidirectional"))
    )
    (net (code "16") (name "/COL3") (class "Default")
      (node (ref "U11F") (pin "D15") (pinfunction "IO_L12N_T1_MRCC_15_D15") (pintype "bidirectional"))
    )
    (net (code "17") (name "/COL4") (class "Default")
      (node (ref "U11F") (pin "B18") (pinfunction "IO_L8N_T1_AD10N_15_B18") (pintype "bidirectional"))
    )
    (net (code "18") (name "/COL5") (class "Default")
      (node (ref "U11F") (pin "D16") (pinfunction "IO_L9P_T1_DQS_AD3P_15_D16") (pintype "bidirectional"))
    )
    (net (code "19") (name "/COL6") (class "Default")
      (node (ref "U11F") (pin "D17") (pinfunction "IO_L9N_T1_DQS_AD3N_15_D17") (pintype "bidirectional"))
    )
    (net (code "20") (name "/COL7") (class "Default")
      (node (ref "U11F") (pin "F13") (pinfunction "IO_L17P_T2_15_F13") (pintype "bidirectional"))
    )
    (net (code "21") (name "/COL8") (class "Default")
      (node (ref "U11F") (pin "E15") (pinfunction "IO_L15N_T2_DQS_15_E15") (pintype "bidirectional"))
    )
    (net (code "22") (name "/COL9") (class "Default")
      (node (ref "U11F") (pin "A13") (pinfunction "IO_L1N_T0_AD0N_15_A13") (pintype "bidirectional"))
    )
    (net (code "23") (name "/COM_CIPO") (class "Default")
      (node (ref "U11F") (pin "P16") (pinfunction "IO_L12N_T1_MRCC_14_P16") (pintype "bidirectional"))
    )
    (net (code "24") (name "/COM_COPI") (class "Default")
      (node (ref "U11F") (pin "N18") (pinfunction "IO_L8N_T1_D12_14_N18") (pintype "bidirectional"))
    )
    (net (code "25") (name "/COM_CS") (class "Default")
      (node (ref "U11F") (pin "T15") (pinfunction "IO_L17N_T2_D29_14_T15") (pintype "bidirectional"))
    )
    (net (code "26") (name "/COM_IRQ") (class "Default")
      (node (ref "U11F") (pin "M16") (pinfunction "IO_L7P_T1_D09_14_M16") (pintype "bidirectional"))
    )
    (net (code "27") (name "/COM_SCLK") (class "Default")
      (node (ref "U11F") (pin "R16") (pinfunction "IO_L14P_T2_SRCC_14_R16") (pintype "bidirectional"))
    )
    (net (code "28") (name "/CRESET_B") (class "Default")
      (node (ref "P12F") (pin "4") (pinfunction "4_4") (pintype "passive"))
      (node (ref "R33F") (pin "1") (pinfunction "1_1") (pintype "passive"))
    )
    (net (code "29") (name "/CRESET_B_F") (class "Default")
      (node (ref "R33F") (pin "2") (pinfunction "2_2") (pintype "passive"))
      (node (ref "U11F") (pin "M6") (pinfunction "IO_L6P_T0_34_M6") (pintype "bidirectional"))
    )
    (net (code "30") (name "/FPGA_DIS") (class "Default")
      (node (ref "Q14F") (pin "1") (pinfunction "G_1") (pintype "passive"))
      (node (ref "Q15F") (pin "1") (pinfunction "G_1") (pintype "passive"))
      (node (ref "R23F") (pin "2") (pinfunction "2_2") (pintype "passive"))
    )
    (net (code "31") (name "/FPGA_SYS_ON") (class "Default")
      (node (ref "Q11F") (pin "1") (pinfunction "G_1") (pintype "passive"))
      (node (ref "R14F") (pin "2") (pinfunction "2_2") (pintype "passive"))
      (node (ref "U11F") (pin "A5") (pinfunction "IO_L9P_T1_DQS_AD7P_35_A5") (pintype "bidirectional"))
    )
    (net (code "32") (name "/F_UART_RX") (class "Default")
      (node (ref "P12F") (pin "2") (pinfunction "2_2") (pintype "passive"))
      (node (ref "U11F") (pin "V7") (pinfunction "IO_L20P_T3_34_V7") (pintype "bidirectional"))
    )
    (net (code "33") (name "/F_UART_TX") (class "Default")
      (node (ref "P12F") (pin "3") (pinfunction "3_3") (pintype "passive"))
      (node (ref "U11F") (pin "V6") (pinfunction "IO_L20N_T3_34_V6") (pintype "bidirectional"))
    )
    (net (code "34") (name "/GPIO0") (class "Default")
      (node (ref "P11F") (pin "14") (pinfunction "14_14") (pintype "passive"))
      (node (ref "U11F") (pin "F14") (pinfunction "IO_L13P_T2_MRCC_15_F14") (pintype "bidirectional"))
    )
    (net (code "35") (name "/GPIO1") (class "Default")
      (node (ref "P11F") (pin "13") (pinfunction "13_13") (pintype "passive"))
      (node (ref "U11F") (pin "F15") (pinfunction "IO_L13N_T2_MRCC_15_F15") (pintype "bidirectional"))
    )
    (net (code "36") (name "/GPIO2") (class "Default")
      (node (ref "P11F") (pin "22") (pinfunction "22_22") (pintype "passive"))
      (node (ref "U11F") (pin "E16") (pinfunction "IO_L10P_T1_AD11P_15_E16") (pintype "bidirectional"))
    )
    (net (code "37") (name "/GPIO3") (class "Default")
      (node (ref "P11F") (pin "12") (pinfunction "12_12") (pintype "passive"))
      (node (ref "U11F") (pin "G15") (pinfunction "IO_L18N_T2_15_G15") (pintype "bidirectional"))
    )
    (net (code "38") (name "/GPIO4") (class "Default")
      (node (ref "P11F") (pin "11") (pinfunction "11_11") (pintype "passive"))
      (node (ref "U11F") (pin "G16") (pinfunction "IO_L14P_T2_SRCC_15_G16") (pintype "bidirectional"))
    )
    (net (code "39") (name "/GPIO5") (class "Default")
      (node (ref "P11F") (pin "10") (pinfunction "10_10") (pintype "passive"))
      (node (ref "U11F") (pin "G13") (pinfunction "IO_0_15_G13") (pintype "bidirectional"))
    )
    (net (code "40") (name "/I2C0_SCL") (class "Default")
      (node (ref "P11F") (pin "18") (pinfunction "18_18") (pintype "passive"))
    )
    (net (code "41") (name "/I2C0_SDA") (class "Default")
      (node (ref "P11F") (pin "17") (pinfunction "17_17") (pintype "passive"))
    )
    (net (code "42") (name "/I2C1_SCL") (class "Default")
      (node (ref "R26F") (pin "1") (pinfunction "1_1") (pintype "passive"))
      (node (ref "U11F") (pin "G2") (pinfunction "IO_L21P_T3_DQS_35_G2") (pintype "bidirectional"))
      (node (ref "U18F") (pin "3") (pinfunction "SCL_3") (pintype "open_collector"))
    )
    (net (code "43") (name "/I2C1_SDA") (class "Default")
      (node (ref "R25F") (pin "1") (pinfunction "1_1") (pintype "passive"))
      (node (ref "U11F") (pin "F2") (pinfunction "IO_L18P_T2_35_F2") (pintype "bidirectional"))
      (node (ref "U18F") (pin "4") (pinfunction "SDA_4") (pintype "open_collector"))
    )
    (net (code "44") (name "/INIT_B") (class "Default")
      (node (ref "R15F") (pin "1") (pinfunction "1_1") (pintype "passive"))
      (node (ref "U11F") (pin "U8") (pinfunction "INIT_B_0_U8") (pintype "open_collector"))
    )
    (net (code "45") (name "/JTAG_TCK") (class "Default")
      (node (ref "P12F") (pin "25") (pinfunction "25_25") (pintype "passive"))
      (node (ref "R35F") (pin "1") (pinfunction "1_1") (pintype "passive"))
      (node (ref "U11F") (pin "D9") (pinfunction "TCK_0_D9") (pintype "input"))
      (node (ref "U11F") (pin "U11") (pinfunction "IO_L24P_T3_D17_14_U11") (pintype "bidirectional"))
    )
    (net (code "46") (name "/JTAG_TDI") (class "Default")
      (node (ref "P12F") (pin "22") (pinfunction "22_22") (pintype "passive"))
      (node (ref "U11F") (pin "P7") (pinfunction "IO_25_34_P7") (pintype "bidirectional"))
      (node (ref "U11F") (pin "R9") (pinfunction "TDI_0_R9") (pintype "input"))
    )
    (net (code "47") (name "/JTAG_TDO") (class "Default")
      (node (ref "P12F") (pin "26") (pinfunction "26_26") (pintype "passive"))
      (node (ref "U11F") (pin "R6") (pinfunction "IO_L23N_T3_34_R6") (pintype "bidirectional"))
      (node (ref "U11F") (pin "T8") (pinfunction "TDO_0_T8") (pintype "output"))
    )
    (net (code "48") (name "/JTAG_TMS") (class "Default")
      (node (ref "P12F") (pin "23") (pinfunction "23_23") (pintype "passive"))
      (node (ref "R34F") (pin "2") (pinfunction "2_2") (pintype "passive"))
      (node (ref "U11F") (pin "P6") (pinfunction "IO_L19P_T3_34_P6") (pintype "bidirectional"))
      (node (ref "U11F") (pin "T9") (pinfunction "TMS_0_T9") (pintype "input"))
    )
    (net (code "49") (name "/KEY0") (class "Default")
      (node (ref "U11F") (pin "A15") (pinfunction "IO_L3N_T0_DQS_AD1N_15_A15") (pintype "bidirectional"))
    )
    (net (code "50") (name "/KEY1") (class "Default")
      (node (ref "U11F") (pin "A17") (pinfunction "IO_L7N_T1_AD2N_15_A17") (pintype "bidirectional"))
    )
    (net (code "51") (name "/KEY2") (class "Default")
      (node (ref "U11F") (pin "A16") (pinfunction "IO_L4N_T0_15_A16") (pintype "bidirectional"))
    )
    (net (code "52") (name "/KEY3") (class "Default")
      (node (ref "U11F") (pin "A14") (pinfunction "IO_L2N_T0_AD8N_15_A14") (pintype "bidirectional"))
    )
    (net (code "53") (name "/KEY4") (class "Default")
      (node (ref "U11F") (pin "C17") (pinfunction "IO_L8P_T1_AD10P_15_C17") (pintype "bidirectional"))
    )
    (net (code "54") (name "/KEY5") (class "Default")
      (node (ref "U11F") (pin "B16") (pinfunction "IO_L4P_T0_15_B16") (pintype "bidirectional"))
    )
    (net (code "55") (name "/KEY6") (class "Default")
      (node (ref "U11F") (pin "B17") (pinfunction "IO_L7P_T1_AD2P_15_B17") (pintype "bidirectional"))
    )
    (net (code "56") (name "/KEY7") (class "Default")
      (node (ref "U11F") (pin "C14") (pinfunction "IO_L6N_T0_VREF_15_C14") (pintype "bidirectional"))
    )
    (net (code "57") (name "/KEY8") (class "Default")
      (node (ref "U11F") (pin "B15") (pinfunction "IO_L3P_T0_DQS_AD1P_15_B15") (pintype "bidirectional"))
    )
    (net (code "58") (name "/LCD_SCLK") (class "Default")
      (node (ref "U11F") (pin "H17") (pinfunction "IO_L22N_T3_15_H17") (pintype "bidirectional"))
    )
    (net (code "59") (name "/LCD_SCS") (class "Default")
      (node (ref "U11F") (pin "G17") (pinfunction "IO_L14N_T2_SRCC_15_G17") (pintype "bidirectional"))
    )
    (net (code "60") (name "/LCD_SI") (class "Default")
      (node (ref "U11F") (pin "H18") (pinfunction "IO_L21P_T3_DQS_15_H18") (pintype "bidirectional"))
    )
    (net (code "61") (name "/NOISE0") (class "Default")
      (node (ref "U11F") (pin "C5") (pinfunction "IO_L2P_T0_AD12P_35_C5") (pintype "bidirectional"))
    )
    (net (code "62") (name "/NOISE1") (class "Default")
      (node (ref "U11F") (pin "A8") (pinfunction "IO_L1P_T0_AD4P_35_A8") (pintype "bidirectional"))
    )
    (net (code "63") (name "/NOISEBIAS_ON") (class "Default")
      (node (ref "U11F") (pin "E17") (pinfunction "IO_L10N_T1_AD11N_15_E17") (pintype "bidirectional"))
    )
    (net (code "64") (name "/NOISE_ON0") (class "Default")
      (node (ref "U11F") (pin "P14") (pinfunction "IO_L11P_T1_SRCC_14_P14") (pintype "bidirectional"))
    )
    (net (code "65") (name "/NOISE_ON1") (class "Default")
      (node (ref "U11F") (pin "R13") (pinfunction "IO_L19N_T3_D25_VREF_14_R13") (pintype "bidirectional"))
    )
    (net (code "66") (name "/PROG_B") (class "Default")
      (node (ref "P12F") (pin "21") (pinfunction "21_21") (pintype "passive"))
      (node (ref "R24F") (pin "1") (pinfunction "1_1") (pintype "passive"))
      (node (ref "U11F") (pin "R8") (pinfunction "PROGRAM_B_0_R8") (pintype "input"))
      (node (ref "U14F") (pin "1") (pinfunction "VOUT_1") (pintype "output"))
    )
    (net (code "67") (name "/PWR_S0") (class "Default")
      (node (ref "R27F") (pin "1") (pinfunction "1_1") (pintype "passive"))
      (node (ref "U11F") (pin "U6") (pinfunction "IO_L24N_T3_34_U6") (pintype "bidirectional"))
      (node (ref "U16F") (pin "C2") (pinfunction "C_C2") (pintype "input"))
      (node (ref "U17F") (pin "C2") (pinfunction "C_C2") (pintype "input"))
    )
    (net (code "68") (name "/PWR_S1") (class "Default")
      (node (ref "U11F") (pin "L13") (pinfunction "IO_0_14_L13") (pintype "bidirectional"))
    )
    (net (code "69") (name "/RES_CT") (class "Default")
      (node (ref "C34F") (pin "1") (pinfunction "1_1") (pintype "passive"))
      (node (ref "U14F") (pin "5") (pinfunction "CT_5") (pintype "passive"))
    )
    (net (code "70") (name "/RTC_3.3V") (class "Default")
      (node (ref "C64F") (pin "1") (pinfunction "1_1") (pintype "passive"))
      (node (ref "C65F") (pin "1") (pinfunction "1_1") (pintype "passive"))
      (node (ref "R32F") (pin "1") (pinfunction "1_1") (pintype "passive"))
      (node (ref "U18F") (pin "1") (pinfunction "VDD_1") (pintype "power_in"))
    )
    (net (code "71") (name "/RTC_INT1") (class "Default")
      (node (ref "R31F") (pin "2") (pinfunction "2_2") (pintype "passive"))
      (node (ref "U11F") (pin "N5") (pinfunction "IO_L10P_T1_34_N5") (pintype "bidirectional"))
      (node (ref "U18F") (pin "2") (pinfunction "~{INT_1}_2") (pintype "output"))
    )
    (net (code "72") (name "/RTC_WAKE_N") (class "Default")
      (node (ref "R29F") (pin "1") (pinfunction "1_1") (pintype "passive"))
      (node (ref "U18F") (pin "6") (pinfunction "~{INT_2}_6") (pintype "output"))
    )
    (net (code "73") (name "/SPINOR_CIPO") (class "Default")
      (node (ref "U11F") (pin "K18") (pinfunction "IO_L1N_T0_D01_DIN_14_K18") (pintype "bidirectional"))
    )
    (net (code "74") (name "/SPINOR_COPI") (class "Default")
      (node (ref "U11F") (pin "K17") (pinfunction "IO_L1P_T0_D00_MOSI_14_K17") (pintype "bidirectional"))
    )
    (net (code "75") (name "/SPINOR_CSN") (class "Default")
      (node (ref "U11F") (pin "M13") (pinfunction "IO_L6P_T0_FCS_B_14_M13") (pintype "bidirectional"))
    )
    (net (code "76") (name "/SPINOR_DQS") (class "Default")
      (node (ref "U11F") (pin "R14") (pinfunction "IO_L13P_T2_MRCC_14_R14") (pintype "bidirectional"))
    )
    (net (code "77") (name "/SPINOR_ECSN") (class "Default")
      (node (ref "R30F") (pin "2") (pinfunction "2_2") (pintype "passive"))
      (node (ref "U11F") (pin "L16") (pinfunction "IO_L3N_T0_DQS_EMCCLK_14_L16") (pintype "bidirectional"))
    )
    (net (code "78") (name "/SPINOR_IO2") (class "Default")
      (node (ref "U11F") (pin "L14") (pinfunction "IO_L2P_T0_D02_14_L14") (pintype "bidirectional"))
    )
    (net (code "79") (name "/SPINOR_IO3") (class "Default")
      (node (ref "U11F") (pin "M15") (pinfunction "IO_L2N_T0_D03_14_M15") (pintype "bidirectional"))
    )
    (net (code "80") (name "/SPINOR_IO4") (class "Default")
      (node (ref "U11F") (pin "L17") (pinfunction "IO_L4P_T0_D04_14_L17") (pintype "bidirectional"))
    )
    (net (code "81") (name "/SPINOR_IO5") (class "Default")
      (node (ref "U11F") (pin "L18") (pinfunction "IO_L4N_T0_D05_14_L18") (pintype "bidirectional"))
    )
    (net (code "82") (name "/SPINOR_IO6") (class "Default")
      (node (ref "U11F") (pin "M14") (pinfunction "IO_L5P_T0_D06_14_M14") (pintype "bidirectional"))
    )
    (net (code "83") (name "/SPINOR_IO7") (class "Default")
      (node (ref "U11F") (pin "N14") (pinfunction "IO_L5N_T0_D07_14_N14") (pintype "bidirectional"))
    )
    (net (code "84") (name "/SPINOR_SCK") (class "Default")
      (node (ref "U11F") (pin "C12") (pinfunction "IO_L13P_T2_MRCC_16_C12") (pintype "bidirectional"))
      (node (ref "U11F") (pin "C8") (pinfunction "CCLK_0_C8") (pintype "input"))
    )
    (net (code "85") (name "/SPK+") (class "Default")
      (node (ref "P11F") (pin "23") (pinfunction "23_23") (pintype "passive"))
      (node (ref "P11F") (pin "24") (pinfunction "24_24") (pintype "passive"))
    )
    (net (code "86") (name "/SPK-") (class "Default")
      (node (ref "P11F") (pin "25") (pinfunction "25_25") (pintype "passive"))
      (node (ref "P11F") (pin "26") (pinfunction "26_26") (pintype "passive"))
    )
    (net (code "87") (name "/SRAM_A0") (class "Default")
      (node (ref "U11F") (pin "V12") (pinfunction "IO_L24N_T3_D16_14_V12") (pintype "bidirectional"))
    )
    (net (code "88") (name "/SRAM_A1") (class "Default")
      (node (ref "U11F") (pin "M5") (pinfunction "IO_L6N_T0_VREF_34_M5") (pintype "bidirectional"))
    )
    (net (code "89") (name "/SRAM_A2") (class "Default")
      (node (ref "U11F") (pin "P5") (pinfunction "IO_L19N_T3_VREF_34_P5") (pintype "bidirectional"))
    )
    (net (code "90") (name "/SRAM_A3") (class "Default")
      (node (ref "U11F") (pin "N4") (pinfunction "IO_L10N_T1_34_N4") (pintype "bidirectional"))
    )
    (net (code "91") (name "/SRAM_A4") (class "Default")
      (node (ref "U11F") (pin "V14") (pinfunction "IO_L20P_T3_D24_14_V14") (pintype "bidirectional"))
    )
    (net (code "92") (name "/SRAM_A5") (class "Default")
      (node (ref "U11F") (pin "M3") (pinfunction "IO_L7P_T1_34_M3") (pintype "bidirectional"))
    )
    (net (code "93") (name "/SRAM_A6") (class "Default")
      (node (ref "U11F") (pin "R17") (pinfunction "IO_L14N_T2_SRCC_14_R17") (pintype "bidirectional"))
    )
    (net (code "94") (name "/SRAM_A7") (class "Default")
      (node (ref "U11F") (pin "U15") (pinfunction "IO_L18P_T2_D28_14_U15") (pintype "bidirectional"))
    )
    (net (code "95") (name "/SRAM_A8") (class "Default")
      (node (ref "U11F") (pin "M4") (pinfunction "IO_L5N_T0_34_M4") (pintype "bidirectional"))
    )
    (net (code "96") (name "/SRAM_A9") (class "Default")
      (node (ref "U11F") (pin "L6") (pinfunction "IO_L4N_T0_34_L6") (pintype "bidirectional"))
    )
    (net (code "97") (name "/SRAM_A10") (class "Default")
      (node (ref "U11F") (pin "K3") (pinfunction "IO_L2P_T0_34_K3") (pintype "bidirectional"))
    )
    (net (code "98") (name "/SRAM_A11") (class "Default")
      (node (ref "U11F") (pin "R18") (pinfunction "IO_L10P_T1_D14_14_R18") (pintype "bidirectional"))
    )
    (net (code "99") (name "/SRAM_A12") (class "Default")
      (node (ref "U11F") (pin "U16") (pinfunction "IO_L16P_T2_CSI_B_14_U16") (pintype "bidirectional"))
    )
    (net (code "100") (name "/SRAM_A13") (class "Default")
      (node (ref "U11F") (pin "K1") (pinfunction "IO_L3P_T0_DQS_34_K1") (pintype "bidirectional"))
    )
    (net (code "101") (name "/SRAM_A14") (class "Default")
      (node (ref "U11F") (pin "R5") (pinfunction "IO_L21P_T3_DQS_34_R5") (pintype "bidirectional"))
    )
    (net (code "102") (name "/SRAM_A15") (class "Default")
      (node (ref "U11F") (pin "T2") (pinfunction "IO_L13N_T2_MRCC_34_T2") (pintype "bidirectional"))
    )
    (net (code "103") (name "/SRAM_A16") (class "Default")
      (node (ref "U11F") (pin "U1") (pinfunction "IO_L14N_T2_SRCC_34_U1") (pintype "bidirectional"))
    )
    (net (code "104") (name "/SRAM_A17") (class "Default")
      (node (ref "U11F") (pin "N1") (pinfunction "IO_L8N_T1_34_N1") (pintype "bidirectional"))
    )
    (net (code "105") (name "/SRAM_A18") (class "Default")
      (node (ref "U11F") (pin "L5") (pinfunction "IO_L5P_T0_34_L5") (pintype "bidirectional"))
    )
    (net (code "106") (name "/SRAM_A19") (class "Default")
      (node (ref "U11F") (pin "K2") (pinfunction "IO_L2N_T0_34_K2") (pintype "bidirectional"))
    )
    (net (code "107") (name "/SRAM_A20") (class "Default")
      (node (ref "U11F") (pin "M18") (pinfunction "IO_L8P_T1_D11_14_M18") (pintype "bidirectional"))
    )
    (net (code "108") (name "/SRAM_A21") (class "Default")
      (node (ref "U11F") (pin "T6") (pinfunction "IO_L22P_T3_34_T6") (pintype "bidirectional"))
    )
    (net (code "109") (name "/SRAM_CE_N") (class "Default")
      (node (ref "U11F") (pin "V5") (pinfunction "IO_L17P_T2_34_V5") (pintype "bidirectional"))
      (node (ref "U16F") (pin "A1") (pinfunction "A_A1") (pintype "passive"))
    )
    (net (code "110") (name "/SRAM_CE_N_1.8") (class "Default")
      (node (ref "U16F") (pin "B1") (pinfunction "B_B1") (pintype "passive"))
    )
    (net (code "111") (name "/SRAM_D0") (class "Default")
      (node (ref "U11F") (pin "M2") (pinfunction "IO_L7N_T1_34_M2") (pintype "bidirectional"))
    )
    (net (code "112") (name "/SRAM_D1") (class "Default")
      (node (ref "U11F") (pin "R4") (pinfunction "IO_L18P_T2_34_R4") (pintype "bidirectional"))
    )
    (net (code "113") (name "/SRAM_D2") (class "Default")
      (node (ref "U11F") (pin "P2") (pinfunction "IO_L11P_T1_SRCC_34_P2") (pintype "bidirectional"))
    )
    (net (code "114") (name "/SRAM_D3") (class "Default")
      (node (ref "U11F") (pin "L4") (pinfunction "IO_L1N_T0_34_L4") (pintype "bidirectional"))
    )
    (net (code "115") (name "/SRAM_D4") (class "Default")
      (node (ref "U11F") (pin "L1") (pinfunction "IO_L3N_T0_DQS_34_L1") (pintype "bidirectional"))
    )
    (net (code "116") (name "/SRAM_D5") (class "Default")
      (node (ref "U11F") (pin "M1") (pinfunction "IO_L8P_T1_34_M1") (pintype "bidirectional"))
    )
    (net (code "117") (name "/SRAM_D6") (class "Default")
      (node (ref "U11F") (pin "R1") (pinfunction "IO_L12N_T1_MRCC_34_R1") (pintype "bidirectional"))
    )
    (net (code "118") (name "/SRAM_D7") (class "Default")
      (node (ref "U11F") (pin "P1") (pinfunction "IO_L11N_T1_SRCC_34_P1") (pintype "bidirectional"))
    )
    (net (code "119") (name "/SRAM_D8") (class "Default")
      (node (ref "U11F") (pin "U3") (pinfunction "IO_L15P_T2_DQS_34_U3") (pintype "bidirectional"))
    )
    (net (code "120") (name "/SRAM_D9") (class "Default")
      (node (ref "U11F") (pin "V2") (pinfunction "IO_L16N_T2_34_V2") (pintype "bidirectional"))
    )
    (net (code "121") (name "/SRAM_D10") (class "Default")
      (node (ref "U11F") (pin "V4") (pinfunction "IO_L17N_T2_34_V4") (pintype "bidirectional"))
    )
    (net (code "122") (name "/SRAM_D11") (class "Default")
      (node (ref "U11F") (pin "U2") (pinfunction "IO_L15N_T2_DQS_34_U2") (pintype "bidirectional"))
    )
    (net (code "123") (name "/SRAM_D12") (class "Default")
      (node (ref "U11F") (pin "N2") (pinfunction "IO_L9N_T1_DQS_34_N2") (pintype "bidirectional"))
    )
    (net (code "124") (name "/SRAM_D13") (class "Default")
      (node (ref "U11F") (pin "T1") (pinfunction "IO_L14P_T2_SRCC_34_T1") (pintype "bidirectional"))
    )
    (net (code "125") (name "/SRAM_D14") (class "Default")
      (node (ref "U11F") (pin "K6") (pinfunction "IO_L4P_T0_34_K6") (pintype "bidirectional"))
    )
    (net (code "126") (name "/SRAM_D15") (class "Default")
      (node (ref "U11F") (pin "J6") (pinfunction "IO_0_34_J6") (pintype "bidirectional"))
    )
    (net (code "127") (name "/SRAM_D16") (class "Default")
      (node (ref "U11F") (pin "V16") (pinfunction "IO_L18N_T2_D27_14_V16") (pintype "bidirectional"))
    )
    (net (code "128") (name "/SRAM_D17") (class "Default")
      (node (ref "U11F") (pin "V15") (pinfunction "IO_L20N_T3_D23_14_V15") (pintype "bidirectional"))
    )
    (net (code "129") (name "/SRAM_D18") (class "Default")
      (node (ref "U11F") (pin "U17") (pinfunction "IO_L15P_T2_DQS_RDWR_B_14_U17") (pintype "bidirectional"))
    )
    (net (code "130") (name "/SRAM_D19") (class "Default")
      (node (ref "U11F") (pin "U18") (pinfunction "IO_L15N_T2_DQS_DOUT_CSO_B_14_U18") (pintype "bidirectional"))
    )
    (net (code "131") (name "/SRAM_D20") (class "Default")
      (node (ref "U11F") (pin "P17") (pinfunction "IO_L9P_T1_DQS_14_P17") (pintype "bidirectional"))
    )
    (net (code "132") (name "/SRAM_D21") (class "Default")
      (node (ref "U11F") (pin "T18") (pinfunction "IO_L10N_T1_D15_14_T18") (pintype "bidirectional"))
    )
    (net (code "133") (name "/SRAM_D22") (class "Default")
      (node (ref "U11F") (pin "P18") (pinfunction "IO_L9N_T1_DQS_D13_14_P18") (pintype "bidirectional"))
    )
    (net (code "134") (name "/SRAM_D23") (class "Default")
      (node (ref "U11F") (pin "M17") (pinfunction "IO_L7N_T1_D10_14_M17") (pintype "bidirectional"))
    )
    (net (code "135") (name "/SRAM_D24") (class "Default")
      (node (ref "U11F") (pin "N3") (pinfunction "IO_L9P_T1_DQS_34_N3") (pintype "bidirectional"))
    )
    (net (code "136") (name "/SRAM_D25") (class "Default")
      (node (ref "U11F") (pin "T4") (pinfunction "IO_L21N_T3_DQS_34_T4") (pintype "bidirectional"))
    )
    (net (code "137") (name "/SRAM_D26") (class "Default")
      (node (ref "U11F") (pin "V13") (pinfunction "IO_L21N_T3_DQS_D22_14_V13") (pintype "bidirectional"))
    )
    (net (code "138") (name "/SRAM_D27") (class "Default")
      (node (ref "U11F") (pin "P15") (pinfunction "IO_L11N_T1_SRCC_14_P15") (pintype "bidirectional"))
    )
    (net (code "139") (name "/SRAM_D28") (class "Default")
      (node (ref "U11F") (pin "T14") (pinfunction "IO_L13N_T2_MRCC_14_T14") (pintype "bidirectional"))
    )
    (net (code "140") (name "/SRAM_D29") (class "Default")
      (node (ref "U11F") (pin "R15") (pinfunction "IO_L17P_T2_D30_14_R15") (pintype "bidirectional"))
    )
    (net (code "141") (name "/SRAM_D30") (class "Default")
      (node (ref "U11F") (pin "T3") (pinfunction "IO_L18N_T2_34_T3") (pintype "bidirectional"))
    )
    (net (code "142") (name "/SRAM_D31") (class "Default")
      (node (ref "U11F") (pin "R7") (pinfunction "IO_L23P_T3_34_R7") (pintype "bidirectional"))
    )
    (net (code "143") (name "/SRAM_DM0") (class "Default")
      (node (ref "U11F") (pin "V3") (pinfunction "IO_L16P_T2_34_V3") (pintype "bidirectional"))
    )
    (net (code "144") (name "/SRAM_DM1") (class "Default")
      (node (ref "U11F") (pin "R2") (pinfunction "IO_L12P_T1_MRCC_34_R2") (pintype "bidirectional"))
    )
    (net (code "145") (name "/SRAM_DM2") (class "Default")
      (node (ref "U11F") (pin "T5") (pinfunction "IO_L22N_T3_34_T5") (pintype "bidirectional"))
    )
    (net (code "146") (name "/SRAM_DM3") (class "Default")
      (node (ref "U11F") (pin "T13") (pinfunction "IO_L22N_T3_D20_14_T13") (pintype "bidirectional"))
    )
    (net (code "147") (name "/SRAM_OE_N") (class "Default")
      (node (ref "U11F") (pin "U12") (pinfunction "IO_L21P_T3_DQS_14_U12") (pintype "bidirectional"))
    )
    (net (code "148") (name "/SRAM_WE_N") (class "Default")
      (node (ref "U11F") (pin "K4") (pinfunction "IO_L1P_T0_34_K4") (pintype "bidirectional"))
    )
    (net (code "149") (name "/SRAM_ZZ_N") (class "Default")
      (node (ref "U11F") (pin "V17") (pinfunction "IO_L16N_T2_D31_14_V17") (pintype "bidirectional"))
      (node (ref "U17F") (pin "A1") (pinfunction "A_A1") (pintype "passive"))
    )
    (net (code "150") (name "/SRAM_ZZ_N_1.8") (class "Default")
      (node (ref "U17F") (pin "B1") (pinfunction "B_B1") (pintype "passive"))
    )
    (net (code "151") (name "/SW_0.95V") (class "Default")
      (node (ref "L12F") (pin "1") (pinfunction "1_1") (pintype "passive"))
      (node (ref "U12F") (pin "B2") (pinfunction "SW_B2") (pintype "output"))
    )
    (net (code "152") (name "/SW_1.8V_F") (class "Default")
      (node (ref "L13F") (pin "1") (pinfunction "1_1") (pintype "passive"))
      (node (ref "U13F") (pin "B2") (pinfunction "SW_B2") (pintype "output"))
    )
    (net (code "153") (name "/T_OFF") (class "Default")
      (node (ref "Q10F") (pin "1") (pinfunction "G_1") (pintype "passive"))
      (node (ref "Q11F") (pin "3") (pinfunction "D_3") (pintype "passive"))
      (node (ref "Q12F") (pin "3") (pinfunction "D_3") (pintype "passive"))
      (node (ref "Q13F") (pin "3") (pinfunction "D_3") (pintype "passive"))
      (node (ref "R10F") (pin "1") (pinfunction "1_1") (pintype "passive"))
      (node (ref "R29F") (pin "2") (pinfunction "2_2") (pintype "passive"))
    )
    (net (code "154") (name "/T_TO_U_ON") (class "Default")
      (node (ref "U11F") (pin "E18") (pinfunction "IO_L16N_T2_15_E18") (pintype "bidirectional"))
    )
    (net (code "155") (name "/UP5K_CIPO") (class "Default")
      (node (ref "P12F") (pin "7") (pinfunction "7_7") (pintype "passive"))
    )
    (net (code "156") (name "/UP5K_COPI") (class "Default")
      (node (ref "P12F") (pin "6") (pinfunction "6_6") (pintype "passive"))
    )
    (net (code "157") (name "/UP5K_CSN") (class "Default")
      (node (ref "P12F") (pin "5") (pinfunction "5_5") (pintype "passive"))
    )
    (net (code "158") (name "/UP5K_KEYCOL0") (class "Default")
      (node (ref "P12F") (pin "19") (pinfunction "19_19") (pintype "passive"))
    )
    (net (code "159") (name "/UP5K_KEYCOL1") (class "Default")
      (node (ref "P12F") (pin "20") (pinfunction "20_20") (pintype "passive"))
    )
    (net (code "160") (name "/UP5K_SCK") (class "Default")
      (node (ref "P12F") (pin "8") (pinfunction "8_8") (pintype "passive"))
    )
    (net (code "161") (name "/USBDN_PD") (class "Default")
      (node (ref "U11F") (pin "A4") (pinfunction "IO_L9N_T1_DQS_AD7N_35_A4") (pintype "bidirectional"))
    )
    (net (code "162") (name "/USBDN_PU") (class "Default")
      (node (ref "U11F") (pin "B2") (pinfunction "IO_L11N_T1_SRCC_35_B2") (pintype "bidirectional"))
    )
    (net (code "163") (name "/USBDP_PD") (class "Default")
      (node (ref "U11F") (pin "C2") (pinfunction "IO_L11P_T1_SRCC_35_C2") (pintype "bidirectional"))
    )
    (net (code "164") (name "/USBDP_PU") (class "Default")
      (node (ref "U11F") (pin "D1") (pinfunction "IO_L14N_T2_SRCC_35_D1") (pintype "bidirectional"))
    )
    (net (code "165") (name "/USB_N") (class "Default")
      (node (ref "U11F") (pin "A3") (pinfunction "IO_L10P_T1_AD15P_35_A3") (pintype "bidirectional"))
      (node (ref "U11F") (pin "B1") (pinfunction "IO_L12N_T1_MRCC_35_B1") (pintype "bidirectional"))
    )
    (net (code "166") (name "/USB_P") (class "Default")
      (node (ref "U11F") (pin "C1") (pinfunction "IO_L12P_T1_MRCC_35_C1") (pintype "bidirectional"))
      (node (ref "U11F") (pin "C3") (pinfunction "IO_L8P_T1_AD14P_35_C3") (pintype "bidirectional"))
    )
    (net (code "167") (name "/U_TO_T_ON") (class "Default")
      (node (ref "Q13F") (pin "1") (pinfunction "G_1") (pintype "passive"))
      (node (ref "R28F") (pin "2") (pinfunction "2_2") (pintype "passive"))
    )
    (net (code "168") (name "/VBUS_DIV") (class "Default")
      (node (ref "U11F") (pin "C4") (pinfunction "IO_L7P_T1_AD6P_35_C4") (pintype "bidirectional"))
    )
    (net (code "169") (name "/VIBE_ON") (class "Default")
      (node (ref "U11F") (pin "H15") (pinfunction "IO_L18P_T2_15_H15") (pintype "bidirectional"))
    )
    (net (code "170") (name "/WIFI_LPCLK") (class "Default")
      (node (ref "U11F") (pin "N15") (pinfunction "IO_L12P_T1_MRCC_14_N15") (pintype "bidirectional"))
    )
    (net (code "171") (name "/XADC_VDD") (class "Default")
      (node (ref "C10F") (pin "1") (pinfunction "1_1") (pintype "passive"))
      (node (ref "C13F") (pin "1") (pinfunction "1_1") (pintype "passive"))
      (node (ref "L10F") (pin "2") (pinfunction "2_2") (pintype "passive"))
      (node (ref "U10F") (pin "1") (pinfunction "IN_1") (pintype "power_in"))
      (node (ref "U11F") (pin "H10") (pinfunction "VCCADC_0_H10") (pintype "power_in"))
    )
    (net (code "172") (name "/XADC_VREF") (class "Default")
      (node (ref "C11F") (pin "1") (pinfunction "1_1") (pintype "passive"))
      (node (ref "C12F") (pin "1") (pinfunction "1_1") (pintype "passive"))
      (node (ref "U10F") (pin "2") (pinfunction "OUT_2") (pintype "power_in"))
      (node (ref "U11F") (pin "K10") (pinfunction "VREFP_0_K10") (pintype "power_in"))
    )
    (net (code "173") (name "GND") (class "Default")
      (node (ref "C14F") (pin "2") (pinfunction "2_2") (pintype "passive"))
      (node (ref "C15F") (pin "2") (pinfunction "2_2") (pintype "passive"))
      (node (ref "C16F") (pin "2") (pinfunction "2_2") (pintype "passive"))
      (node (ref "C17F") (pin "2") (pinfunction "2_2") (pintype "passive"))
      (node (ref "C18F") (pin "2") (pinfunction "2_2") (pintype "passive"))
      (node (ref "C19F") (pin "2") (pinfunction "2_2") (pintype "passive"))
      (node (ref "C20F") (pin "2") (pinfunction "2_2") (pintype "passive"))
      (node (ref "C21F") (pin "2") (pinfunction "2_2") (pintype "passive"))
      (node (ref "C22F") (pin "1") (pinfunction "1_1") (pintype "passive"))
      (node (ref "C23F") (pin "2") (pinfunction "2_2") (pintype "passive"))
      (node (ref "C24F") (pin "2") (pinfunction "2_2") (pintype "passive"))
      (node (ref "C25F") (pin "2") (pinfunction "2_2") (pintype "passive"))
      (node (ref "C26F") (pin "2") (pinfunction "2_2") (pintype "passive"))
      (node (ref "C27F") (pin "1") (pinfunction "1_1") (pintype "passive"))
      (node (ref "C28F") (pin "2") (pinfunction "2_2") (pintype "passive"))
      (node (ref "C29F") (pin "2") (pinfunction "2_2") (pintype "passive"))
      (node (ref "C30F") (pin "1") (pinfunction "1_1") (pintype "passive"))
      (node (ref "C31F") (pin "2") (pinfunction "2_2") (pintype "passive"))
      (node (ref "C32F") (pin "2") (pinfunction "2_2") (pintype "passive"))
      (node (ref "C33F") (pin "2") (pinfunction "2_2") (pintype "passive"))
      (node (ref "C34F") (pin "2") (pinfunction "2_2") (pintype "passive"))
      (node (ref "C35F") (pin "2") (pinfunction "2_2") (pintype "passive"))
      (node (ref "C36F") (pin "2") (pinfunction "2_2") (pintype "passive"))
      (node (ref "C37F") (pin "1") (pinfunction "1_1") (pintype "passive"))
      (node (ref "C38F") (pin "2") (pinfunction "2_2") (pintype "passive"))
      (node (ref "C39F") (pin "2") (pinfunction "2_2") (pintype "passive"))
      (node (ref "C40F") (pin "1") (pinfunction "1_1") (pintype "passive"))
      (node (ref "C41F") (pin "2") (pinfunction "2_2") (pintype "passive"))
      (node (ref "C42F") (pin "2") (pinfunction "2_2") (pintype "passive"))
      (node (ref "C43F") (pin "2") (pinfunction "2_2") (pintype "passive"))
      (node (ref "C44F") (pin "2") (pinfunction "2_2") (pintype "passive"))
      (node (ref "C45F") (pin "2") (pinfunction "2_2") (pintype "passive"))
      (node (ref "C46F") (pin "2") (pinfunction "2_2") (pintype "passive"))
      (node (ref "C47F") (pin "1") (pinfunction "1_1") (pintype "passive"))
      (node (ref "C48F") (pin "2") (pinfunction "2_2") (pintype "passive"))
      (node (ref "C49F") (pin "2") (pinfunction "2_2") (pintype "passive"))
      (node (ref "C50F") (pin "2") (pinfunction "2_2") (pintype "passive"))
      (node (ref "C51F") (pin "2") (pinfunction "2_2") (pintype "passive"))
      (node (ref "C52F") (pin "1") (pinfunction "1_1") (pintype "passive"))
      (node (ref "C53F") (pin "2") (pinfunction "2_2") (pintype "passive"))
      (node (ref "C54F") (pin "2") (pinfunction "2_2") (pintype "passive"))
      (node (ref "C55F") (pin "1") (pinfunction "1_1") (pintype "passive"))
      (node (ref "C56F") (pin "2") (pinfunction "2_2") (pintype "passive"))
      (node (ref "C57F") (pin "2") (pinfunction "2_2") (pintype "passive"))
      (node (ref "C58F") (pin "2") (pinfunction "2_2") (pintype "passive"))
      (node (ref "C59F") (pin "2") (pinfunction "2_2") (pintype "passive"))
      (node (ref "C60F") (pin "2") (pinfunction "2_2") (pintype "passive"))
      (node (ref "C61F") (pin "2") (pinfunction "2_2") (pintype "passive"))
      (node (ref "C62F") (pin "2") (pinfunction "2_2") (pintype "passive"))
      (node (ref "C63F") (pin "2") (pinfunction "2_2") (pintype "passive"))
      (node (ref "C64F") (pin "2") (pinfunction "2_2") (pintype "passive"))
      (node (ref "C65F") (pin "2") (pinfunction "2_2") (pintype "passive"))
      (node (ref "C66F") (pin "2") (pinfunction "2_2") (pintype "passive"))
      (node (ref "C67F") (pin "1") (pinfunction "1_1") (pintype "passive"))
      (node (ref "C68F") (pin "2") (pinfunction "2_2") (pintype "passive"))
      (node (ref "C71F") (pin "1") (pinfunction "1_1") (pintype "passive"))
      (node (ref "C72F") (pin "2") (pinfunction "2_2") (pintype "passive"))
      (node (ref "C73F") (pin "2") (pinfunction "2_2") (pintype "passive"))
      (node (ref "C74F") (pin "2") (pinfunction "2_2") (pintype "passive"))
      (node (ref "L11F") (pin "1") (pinfunction "1_1") (pintype "passive"))
      (node (ref "P11F") (pin "1") (pinfunction "1_1") (pintype "passive"))
      (node (ref "P11F") (pin "15") (pinfunction "15_15") (pintype "passive"))
      (node (ref "P11F") (pin "2") (pinfunction "2_2") (pintype "passive"))
      (node (ref "P11F") (pin "21") (pinfunction "21_21") (pintype "passive"))
      (node (ref "P11F") (pin "3") (pinfunction "3_3") (pintype "passive"))
      (node (ref "P11F") (pin "8") (pinfunction "8_8") (pintype "passive"))
      (node (ref "P12F") (pin "1") (pinfunction "1_1") (pintype "passive"))
      (node (ref "P12F") (pin "11") (pinfunction "11_11") (pintype "passive"))
      (node (ref "P12F") (pin "16") (pinfunction "16_16") (pintype "passive"))
      (node (ref "P12F") (pin "17") (pinfunction "17_17") (pintype "passive"))
      (node (ref "P12F") (pin "24") (pinfunction "24_24") (pintype "passive"))
      (node (ref "Q11F") (pin "2") (pinfunction "S_2") (pintype "passive"))
      (node (ref "Q12F") (pin "2") (pinfunction "S_2") (pintype "passive"))
      (node (ref "Q13F") (pin "2") (pinfunction "S_2") (pintype "passive"))
      (node (ref "Q14F") (pin "2") (pinfunction "S_2") (pintype "passive"))
      (node (ref "Q15F") (pin "2") (pinfunction "S_2") (pintype "passive"))
      (node (ref "R11F") (pin "2") (pinfunction "2_2") (pintype "passive"))
      (node (ref "R14F") (pin "1") (pinfunction "1_1") (pintype "passive"))
      (node (ref "R17F") (pin "1") (pinfunction "1_1") (pintype "passive"))
      (node (ref "R18F") (pin "1") (pinfunction "1_1") (pintype "passive"))
      (node (ref "R23F") (pin "1") (pinfunction "1_1") (pintype "passive"))
      (node (ref "R27F") (pin "2") (pinfunction "2_2") (pintype "passive"))
      (node (ref "R28F") (pin "1") (pinfunction "1_1") (pintype "passive"))
      (node (ref "R35F") (pin "2") (pinfunction "2_2") (pintype "passive"))
      (node (ref "U11F") (pin "A1") (pinfunction "GND_A1") (pintype "power_in"))
      (node (ref "U11F") (pin "A12") (pinfunction "GND_A12") (pintype "power_in"))
      (node (ref "U11F") (pin "A18") (pinfunction "GND_A18") (pintype "power_in"))
      (node (ref "U11F") (pin "A2") (pinfunction "IO_L10N_T1_AD15N_35_A2") (pintype "bidirectional"))
      (node (ref "U11F") (pin "A7") (pinfunction "IO_L1N_T0_AD4N_35_A7") (pintype "bidirectional"))
      (node (ref "U11F") (pin "B3") (pinfunction "IO_L8N_T1_AD14N_35_B3") (pintype "bidirectional"))
      (node (ref "U11F") (pin "B4") (pinfunction "IO_L7N_T1_AD6N_35_B4") (pintype "bidirectional"))
      (node (ref "U11F") (pin "B5") (pinfunction "IO_L2N_T0_AD12N_35_B5") (pintype "bidirectional"))
      (node (ref "U11F") (pin "B8") (pinfunction "VCCBATT_0_B8") (pintype "power_in"))
      (node (ref "U11F") (pin "B9") (pinfunction "GND_B9") (pintype "power_in"))
      (node (ref "U11F") (pin "C16") (pinfunction "GND_C16") (pintype "power_in"))
      (node (ref "U11F") (pin "C6") (pinfunction "GND_C6") (pintype "power_in"))
      (node (ref "U11F") (pin "D13") (pinfunction "GND_D13") (pintype "power_in"))
      (node (ref "U11F") (pin "D3") (pinfunction "GND_D3") (pintype "power_in"))
      (node (ref "U11F") (pin "E10") (pinfunction "GND_E10") (pintype "power_in"))
      (node (ref "U11F") (pin "E8") (pinfunction "GND_E8") (pintype "power_in"))
      (node (ref "U11F") (pin "F11") (pinfunction "GND_F11") (pintype "power_in"))
      (node (ref "U11F") (pin "F17") (pinfunction "GND_F17") (pintype "power_in"))
      (node (ref "U11F") (pin "F7") (pinfunction "GND_F7") (pintype "power_in"))
      (node (ref "U11F") (pin "F9") (pinfunction "GND_F9") (pintype "power_in"))
      (node (ref "U11F") (pin "G10") (pinfunction "GND_G10") (pintype "power_in"))
      (node (ref "U11F") (pin "G12") (pinfunction "GND_G12") (pintype "power_in"))
      (node (ref "U11F") (pin "G14") (pinfunction "GND_G14") (pintype "power_in"))
      (node (ref "U11F") (pin "G4") (pinfunction "GND_G4") (pintype "power_in"))
      (node (ref "U11F") (pin "G8") (pinfunction "GND_G8") (pintype "power_in"))
      (node (ref "U11F") (pin "H1") (pinfunction "GND_H1") (pintype "power_in"))
      (node (ref "U11F") (pin "H11") (pinfunction "GND_H11") (pintype "power_in"))
      (node (ref "U11F") (pin "H7") (pinfunction "GND_H7") (pintype "power_in"))
      (node (ref "U11F") (pin "J12") (pinfunction "GND_J12") (pintype "power_in"))
      (node (ref "U11F") (pin "J18") (pinfunction "GND_J18") (pintype "power_in"))
      (node (ref "U11F") (pin "J8") (pinfunction "GND_J8") (pintype "power_in"))
      (node (ref "U11F") (pin "K11") (pinfunction "GND_K11") (pintype "power_in"))
      (node (ref "U11F") (pin "K15") (pinfunction "GND_K15") (pintype "power_in"))
      (node (ref "U11F") (pin "K5") (pinfunction "GND_K5") (pintype "power_in"))
      (node (ref "U11F") (pin "K7") (pinfunction "GND_K7") (pintype "power_in"))
      (node (ref "U11F") (pin "L12") (pinfunction "GND_L12") (pintype "power_in"))
      (node (ref "U11F") (pin "L2") (pinfunction "GND_L2") (pintype "power_in"))
      (node (ref "U11F") (pin "L8") (pinfunction "GND_L8") (pintype "power_in"))
      (node (ref "U11F") (pin "M11") (pinfunction "GND_M11") (pintype "power_in"))
      (node (ref "U11F") (pin "M7") (pinfunction "GND_M7") (pintype "power_in"))
      (node (ref "U11F") (pin "M9") (pinfunction "GND_M9") (pintype "power_in"))
      (node (ref "U11F") (pin "N10") (pinfunction "GND_N10") (pintype "power_in"))
      (node (ref "U11F") (pin "N12") (pinfunction "GND_N12") (pintype "power_in"))
      (node (ref "U11F") (pin "N16") (pinfunction "GND_N16") (pintype "power_in"))
      (node (ref "U11F") (pin "N6") (pinfunction "GND_N6") (pintype "power_in"))
      (node (ref "U11F") (pin "N8") (pinfunction "GND_N8") (pintype "power_in"))
      (node (ref "U11F") (pin "P11") (pinfunction "GND_P11") (pintype "power_in"))
      (node (ref "U11F") (pin "P3") (pinfunction "GND_P3") (pintype "power_in"))
      (node (ref "U11F") (pin "P9") (pinfunction "GND_P9") (pintype "power_in"))
      (node (ref "U11F") (pin "R10") (pinfunction "GND_R10") (pintype "power_in"))
      (node (ref "U11F") (pin "T17") (pinfunction "GND_T17") (pintype "power_in"))
      (node (ref "U11F") (pin "T7") (pinfunction "GND_T7") (pintype "power_in"))
      (node (ref "U11F") (pin "U14") (pinfunction "GND_U14") (pintype "power_in"))
      (node (ref "U11F") (pin "U4") (pinfunction "GND_U4") (pintype "power_in"))
      (node (ref "U11F") (pin "V1") (pinfunction "GND_V1") (pintype "power_in"))
      (node (ref "U11F") (pin "V11") (pinfunction "GND_V11") (pintype "power_in"))
      (node (ref "U11F") (pin "V18") (pinfunction "GND_V18") (pintype "power_in"))
      (node (ref "U11F") (pin "V9") (pinfunction "CFGBVS_0_V9") (pintype "input"))
      (node (ref "U12F") (pin "A1") (pinfunction "GND_A1") (pintype "power_in"))
      (node (ref "U13F") (pin "A1") (pinfunction "GND_A1") (pintype "power_in"))
      (node (ref "U13F") (pin "C1") (pinfunction "VSEL/MODE_C1") (pintype "input"))
      (node (ref "U14F") (pin "3") (pinfunction "GND_3") (pintype "power_in"))
      (node (ref "U15F") (pin "1") (pinfunction "ST_1") (pintype "input"))
      (node (ref "U15F") (pin "4") (pinfunction "GND_4") (pintype "power_in"))
      (node (ref "U16F") (pin "C1") (pinfunction "GND_C1") (pintype "power_in"))
      (node (ref "U17F") (pin "C1") (pinfunction "GND_C1") (pintype "power_in"))
      (node (ref "U18F") (pin "7") (pinfunction "VSS_7") (pintype "power_in"))
    )
    (net (code "174") (name "Net-(Q14F-D)") (class "Default")
      (node (ref "Q14F") (pin "3") (pinfunction "D_3") (pintype "passive"))
      (node (ref "R20F") (pin "1") (pinfunction "1_1") (pintype "passive"))
    )
    (net (code "175") (name "Net-(Q15F-D)") (class "Default")
      (node (ref "Q15F") (pin "3") (pinfunction "D_3") (pintype "passive"))
      (node (ref "R21F") (pin "1") (pinfunction "1_1") (pintype "passive"))
    )
    (net (code "176") (name "Net-(U11FA-DONE_0)") (class "Default")
      (node (ref "R13F") (pin "1") (pinfunction "1_1") (pintype "passive"))
      (node (ref "U11F") (pin "V8") (pinfunction "DONE_0_V8") (pintype "open_collector"))
    )
    (net (code "177") (name "Net-(U11FA-M0_0)") (class "Default")
      (node (ref "R19F") (pin "2") (pinfunction "2_2") (pintype "passive"))
      (node (ref "U11F") (pin "T10") (pinfunction "M0_0_T10") (pintype "input"))
    )
    (net (code "178") (name "Net-(U11FA-M1_0)") (class "Default")
      (node (ref "R18F") (pin "2") (pinfunction "2_2") (pintype "passive"))
      (node (ref "U11F") (pin "U10") (pinfunction "M1_0_U10") (pintype "input"))
    )
    (net (code "179") (name "Net-(U11FA-M2_0)") (class "Default")
      (node (ref "R17F") (pin "2") (pinfunction "2_2") (pintype "passive"))
      (node (ref "U11F") (pin "U9") (pinfunction "M2_0_U9") (pintype "input"))
    )
    (net (code "180") (name "Net-(U11FB-IO_L3P_T0_DQS_PUDC_B_14)") (class "Default")
      (node (ref "R22F") (pin "1") (pinfunction "1_1") (pintype "passive"))
      (node (ref "U11F") (pin "L15") (pinfunction "IO_L3P_T0_DQS_PUDC_B_14_L15") (pintype "bidirectional"))
    )
    (net (code "181") (name "Net-(U12F-EN)") (class "Default")
      (node (ref "R12F") (pin "1") (pinfunction "1_1") (pintype "passive"))
      (node (ref "U12F") (pin "C2") (pinfunction "EN_C2") (pintype "input"))
    )
    (net (code "182") (name "Net-(U12F-VSEL{slash}MODE)") (class "Default")
      (node (ref "R11F") (pin "1") (pinfunction "1_1") (pintype "passive"))
      (node (ref "U12F") (pin "C1") (pinfunction "VSEL/MODE_C1") (pintype "input"))
    )
    (net (code "183") (name "Net-(U13F-EN)") (class "Default")
      (node (ref "R16F") (pin "2") (pinfunction "2_2") (pintype "passive"))
      (node (ref "U13F") (pin "C2") (pinfunction "EN_C2") (pintype "input"))
    )
    (net (code "184") (name "P0.95V_T") (class "Default")
      (node (ref "C16F") (pin "1") (pinfunction "1_1") (pintype "passive"))
      (node (ref "C19F") (pin "1") (pinfunction "1_1") (pintype "passive"))
      (node (ref "C20F") (pin "1") (pinfunction "1_1") (pintype "passive"))
      (node (ref "C21F") (pin "1") (pinfunction "1_1") (pintype "passive"))
      (node (ref "C22F") (pin "2") (pinfunction "2_2") (pintype "passive"))
      (node (ref "C23F") (pin "1") (pinfunction "1_1") (pintype "passive"))
      (node (ref "C24F") (pin "1") (pinfunction "1_1") (pintype "passive"))
      (node (ref "C25F") (pin "1") (pinfunction "1_1") (pintype "passive"))
      (node (ref "C26F") (pin "1") (pinfunction "1_1") (pintype "passive"))
      (node (ref "C27F") (pin "2") (pinfunction "2_2") (pintype "passive"))
      (node (ref "C28F") (pin "1") (pinfunction "1_1") (pintype "passive"))
      (node (ref "C60F") (pin "1") (pinfunction "1_1") (pintype "passive"))
      (node (ref "C61F") (pin "1") (pinfunction "1_1") (pintype "passive"))
      (node (ref "L12F") (pin "2") (pinfunction "2_2") (pintype "passive"))
      (node (ref "R16F") (pin "1") (pinfunction "1_1") (pintype "passive"))
      (node (ref "R20F") (pin "2") (pinfunction "2_2") (pintype "passive"))
      (node (ref "U11F") (pin "E11") (pinfunction "VCCINT_E11") (pintype "power_in"))
      (node (ref "U11F") (pin "E7") (pinfunction "VCCINT_E7") (pintype "power_in"))
      (node (ref "U11F") (pin "E9") (pinfunction "VCCINT_E9") (pintype "power_in"))
      (node (ref "U11F") (pin "F10") (pinfunction "VCCINT_F10") (pintype "power_in"))
      (node (ref "U11F") (pin "F8") (pinfunction "VCCINT_F8") (pintype "power_in"))
      (node (ref "U11F") (pin "G11") (pinfunction "VCCINT_G11") (pintype "power_in"))
      (node (ref "U11F") (pin "G7") (pinfunction "VCCINT_G7") (pintype "power_in"))
      (node (ref "U11F") (pin "G9") (pinfunction "VCCINT_G9") (pintype "power_in"))
      (node (ref "U11F") (pin "H8") (pinfunction "VCCINT_H8") (pintype "power_in"))
      (node (ref "U11F") (pin "J11") (pinfunction "VCCINT_J11") (pintype "power_in"))
      (node (ref "U11F") (pin "J7") (pinfunction "VCCINT_J7") (pintype "power_in"))
      (node (ref "U11F") (pin "K8") (pinfunction "VCCINT_K8") (pintype "power_in"))
      (node (ref "U11F") (pin "L11") (pinfunction "VCCINT_L11") (pintype "power_in"))
      (node (ref "U11F") (pin "L7") (pinfunction "VCCBRAM_L7") (pintype "power_in"))
      (node (ref "U11F") (pin "M10") (pinfunction "VCCINT_M10") (pintype "power_in"))
      (node (ref "U11F") (pin "M8") (pinfunction "VCCINT_M8") (pintype "power_in"))
      (node (ref "U11F") (pin "N11") (pinfunction "VCCINT_N11") (pintype "power_in"))
      (node (ref "U11F") (pin "N7") (pinfunction "VCCBRAM_N7") (pintype "power_in"))
      (node (ref "U11F") (pin "N9") (pinfunction "VCCINT_N9") (pintype "power_in"))
      (node (ref "U11F") (pin "P10") (pinfunction "VCCINT_P10") (pintype "power_in"))
      (node (ref "U11F") (pin "P8") (pinfunction "VCCINT_P8") (pintype "power_in"))
      (node (ref "U12F") (pin "A2") (pinfunction "VOS_A2") (pintype "input"))
    )
    (net (code "185") (name "P1.8V") (class "Default")
      (node (ref "C37F") (pin "2") (pinfunction "2_2") (pintype "passive"))
      (node (ref "P11F") (pin "16") (pinfunction "16_16") (pintype "passive"))
      (node (ref "P12F") (pin "9") (pinfunction "9_9") (pintype "passive"))
    )
    (net (code "186") (name "P1.8V_SBY") (class "Default")
      (node (ref "U16F") (pin "A2") (pinfunction "VCC_A2") (pintype "power_in"))
      (node (ref "U17F") (pin "A2") (pinfunction "VCC_A2") (pintype "power_in"))
    )
    (net (code "187") (name "P1.8V_T") (class "Default")
      (node (ref "C18F") (pin "1") (pinfunction "1_1") (pintype "passive"))
      (node (ref "C29F") (pin "1") (pinfunction "1_1") (pintype "passive"))
      (node (ref "C30F") (pin "2") (pinfunction "2_2") (pintype "passive"))
      (node (ref "C31F") (pin "1") (pinfunction "1_1") (pintype "passive"))
      (node (ref "C32F") (pin "1") (pinfunction "1_1") (pintype "passive"))
      (node (ref "C33F") (pin "1") (pinfunction "1_1") (pintype "passive"))
      (node (ref "C35F") (pin "1") (pinfunction "1_1") (pintype "passive"))
      (node (ref "C38F") (pin "1") (pinfunction "1_1") (pintype "passive"))
      (node (ref "C39F") (pin "1") (pinfunction "1_1") (pintype "passive"))
      (node (ref "C40F") (pin "2") (pinfunction "2_2") (pintype "passive"))
      (node (ref "C41F") (pin "1") (pinfunction "1_1") (pintype "passive"))
      (node (ref "C42F") (pin "1") (pinfunction "1_1") (pintype "passive"))
      (node (ref "C43F") (pin "1") (pinfunction "1_1") (pintype "passive"))
      (node (ref "C44F") (pin "1") (pinfunction "1_1") (pintype "passive"))
      (node (ref "C52F") (pin "2") (pinfunction "2_2") (pintype "passive"))
      (node (ref "C53F") (pin "1") (pinfunction "1_1") (pintype "passive"))
      (node (ref "C54F") (pin "1") (pinfunction "1_1") (pintype "passive"))
      (node (ref "C55F") (pin "2") (pinfunction "2_2") (pintype "passive"))
      (node (ref "C56F") (pin "1") (pinfunction "1_1") (pintype "passive"))
      (node (ref "C57F") (pin "1") (pinfunction "1_1") (pintype "passive"))
      (node (ref "C58F") (pin "1") (pinfunction "1_1") (pintype "passive"))
      (node (ref "C59F") (pin "1") (pinfunction "1_1") (pintype "passive"))
      (node (ref "C62F") (pin "1") (pinfunction "1_1") (pintype "passive"))
      (node (ref "C67F") (pin "2") (pinfunction "2_2") (pintype "passive"))
      (node (ref "C68F") (pin "1") (pinfunction "1_1") (pintype "passive"))
      (node (ref "L10F") (pin "1") (pinfunction "1_1") (pintype "passive"))
      (node (ref "L13F") (pin "2") (pinfunction "2_2") (pintype "passive"))
      (node (ref "P12F") (pin "18") (pinfunction "18_18") (pintype "passive"))
      (node (ref "R13F") (pin "2") (pinfunction "2_2") (pintype "passive"))
      (node (ref "R15F") (pin "2") (pinfunction "2_2") (pintype "passive"))
      (node (ref "R19F") (pin "1") (pinfunction "1_1") (pintype "passive"))
      (node (ref "R21F") (pin "2") (pinfunction "2_2") (pintype "passive"))
      (node (ref "R22F") (pin "2") (pinfunction "2_2") (pintype "passive"))
      (node (ref "R24F") (pin "2") (pinfunction "2_2") (pintype "passive"))
      (node (ref "R30F") (pin "1") (pinfunction "1_1") (pintype "passive"))
      (node (ref "R31F") (pin "1") (pinfunction "1_1") (pintype "passive"))
      (node (ref "R34F") (pin "1") (pinfunction "1_1") (pintype "passive"))
      (node (ref "U11F") (pin "B10") (pinfunction "VCCO_16_B10") (pintype "power_in"))
      (node (ref "U11F") (pin "B12") (pinfunction "VCCO_16_B12") (pintype "power_in"))
      (node (ref "U11F") (pin "D8") (pinfunction "VCCO_0_D8") (pintype "power_in"))
      (node (ref "U11F") (pin "F12") (pinfunction "VCCAUX_F12") (pintype "power_in"))
      (node (ref "U11F") (pin "H12") (pinfunction "VCCAUX_H12") (pintype "power_in"))
      (node (ref "U11F") (pin "K12") (pinfunction "VCCAUX_K12") (pintype "power_in"))
      (node (ref "U11F") (pin "L3") (pinfunction "VCCO_34_L3") (pintype "power_in"))
      (node (ref "U11F") (pin "M12") (pinfunction "VCCAUX_M12") (pintype "power_in"))
      (node (ref "U11F") (pin "N17") (pinfunction "VCCO_14_N17") (pintype "power_in"))
      (node (ref "U11F") (pin "P12") (pinfunction "VCCAUX_P12") (pintype "power_in"))
      (node (ref "U11F") (pin "P4") (pinfunction "VCCO_34_P4") (pintype "power_in"))
      (node (ref "U11F") (pin "T16") (pinfunction "VCCO_14_T16") (pintype "power_in"))
      (node (ref "U11F") (pin "U13") (pinfunction "VCCO_14_U13") (pintype "power_in"))
      (node (ref "U11F") (pin "U5") (pinfunction "VCCO_34_U5") (pintype "power_in"))
      (node (ref "U11F") (pin "V10") (pinfunction "VCCO_0_V10") (pintype "power_in"))
      (node (ref "U13F") (pin "A2") (pinfunction "VOS_A2") (pintype "input"))
      (node (ref "U14F") (pin "2") (pinfunction "VDD_2") (pintype "power_in"))
      (node (ref "U15F") (pin "3") (pinfunction "VDD_3") (pintype "power_in"))
    )
    (net (code "188") (name "P3.3V") (class "Default")
      (node (ref "P11F") (pin "9") (pinfunction "9_9") (pintype "passive"))
    )
    (net (code "189") (name "P3.3V_A") (class "Default")
      (node (ref "C45F") (pin "1") (pinfunction "1_1") (pintype "passive"))
      (node (ref "C46F") (pin "1") (pinfunction "1_1") (pintype "passive"))
      (node (ref "C47F") (pin "2") (pinfunction "2_2") (pintype "passive"))
      (node (ref "C48F") (pin "1") (pinfunction "1_1") (pintype "passive"))
      (node (ref "C49F") (pin "1") (pinfunction "1_1") (pintype "passive"))
      (node (ref "C50F") (pin "1") (pinfunction "1_1") (pintype "passive"))
      (node (ref "C51F") (pin "1") (pinfunction "1_1") (pintype "passive"))
      (node (ref "C71F") (pin "2") (pinfunction "2_2") (pintype "passive"))
      (node (ref "C72F") (pin "1") (pinfunction "1_1") (pintype "passive"))
      (node (ref "C73F") (pin "1") (pinfunction "1_1") (pintype "passive"))
      (node (ref "C74F") (pin "1") (pinfunction "1_1") (pintype "passive"))
      (node (ref "R25F") (pin "2") (pinfunction "2_2") (pintype "passive"))
      (node (ref "R26F") (pin "2") (pinfunction "2_2") (pintype "passive"))
      (node (ref "R32F") (pin "2") (pinfunction "2_2") (pintype "passive"))
      (node (ref "U11F") (pin "B6") (pinfunction "VCCO_35_B6") (pintype "power_in"))
      (node (ref "U11F") (pin "C15") (pinfunction "VCCO_15_C15") (pintype "power_in"))
      (node (ref "U11F") (pin "D4") (pinfunction "VCCO_35_D4") (pintype "power_in"))
      (node (ref "U11F") (pin "F16") (pinfunction "VCCO_15_F16") (pintype "power_in"))
      (node (ref "U11F") (pin "G3") (pinfunction "VCCO_35_G3") (pintype "power_in"))
      (node (ref "U11F") (pin "J17") (pinfunction "VCCO_15_J17") (pintype "power_in"))
    )
    (net (code "190") (name "PACK_P") (class "Default")
      (node (ref "P11F") (pin "4") (pinfunction "4_4") (pintype "passive"))
      (node (ref "P11F") (pin "5") (pinfunction "5_5") (pintype "passive"))
      (node (ref "P11F") (pin "6") (pinfunction "6_6") (pintype "passive"))
    )
    (net (code "191") (name "VBAT") (class "Default")
      (node (ref "C66F") (pin "1") (pinfunction "1_1") (pintype "passive"))
      (node (ref "U18F") (pin "8") (pinfunction "VBACKUP_8") (pintype "power_in"))
    )
    (net (code "192") (name "VBUS") (class "Default")
      (node (ref "C63F") (pin "1") (pinfunction "1_1") (pintype "passive"))
      (node (ref "P12F") (pin "12") (pinfunction "12_12") (pintype "passive"))
      (node (ref "P12F") (pin "13") (pinfunction "13_13") (pintype "passive"))
      (node (ref "P12F") (pin "14") (pinfunction "14_14") (pintype "passive"))
      (node (ref "Q12F") (pin "1") (pinfunction "G_1") (pintype "passive"))
    )
    (net (code "193") (name "VSYS_RAW") (class "Default")
      (node (ref "C36F") (pin "1") (pinfunction "1_1") (pintype "passive"))
      (node (ref "J10F") (pin "1") (pinfunction "1_1") (pintype "passive"))
      (node (ref "Q10F") (pin "4") (pinfunction "S_4") (pintype "passive"))
      (node (ref "R10F") (pin "2") (pinfunction "2_2") (pintype "passive"))
    )
    (net (code "194") (name "VSYS_T") (class "Default")
      (node (ref "C14F") (pin "1") (pinfunction "1_1") (pintype "passive"))
      (node (ref "C15F") (pin "1") (pinfunction "1_1") (pintype "passive"))
      (node (ref "C17F") (pin "1") (pinfunction "1_1") (pintype "passive"))
      (node (ref "J11F") (pin "1") (pinfunction "1_1") (pintype "passive"))
      (node (ref "J12F") (pin "1") (pinfunction "1_1") (pintype "passive"))
      (node (ref "Q10F") (pin "2") (pinfunction "D_2") (pintype "passive"))
      (node (ref "Q10F") (pin "3") (pinfunction "D_3") (pintype "passive"))
      (node (ref "R12F") (pin "2") (pinfunction "2_2") (pintype "passive"))
      (node (ref "U12F") (pin "B1") (pinfunction "VIN_B1") (pintype "power_in"))
      (node (ref "U13F") (pin "B1") (pinfunction "VIN_B1") (pintype "power_in"))
    )
    (net (code "195") (name "VSYS_U") (class "Default")
      (node (ref "P11F") (pin "20") (pinfunction "20_20") (pintype "passive"))
    )
    (net (code "196") (name "XADC_GND") (class "Default")
      (node (ref "C10F") (pin "2") (pinfunction "2_2") (pintype "passive"))
      (node (ref "C11F") (pin "2") (pinfunction "2_2") (pintype "passive"))
      (node (ref "C12F") (pin "2") (pinfunction "2_2") (pintype "passive"))
      (node (ref "C13F") (pin "2") (pinfunction "2_2") (pintype "passive"))
      (node (ref "L11F") (pin "2") (pinfunction "2_2") (pintype "passive"))
      (node (ref "U10F") (pin "3") (pinfunction "GND_3") (pintype "power_in"))
      (node (ref "U11F") (pin "H9") (pinfunction "GNDADC_0_H9") (pintype "power_in"))
      (node (ref "U11F") (pin "J9") (pinfunction "VREFN_0_J9") (pintype "power_in"))
      (node (ref "U11F") (pin "L10") (pinfunction "DXP_0_L10") (pintype "passive"))
      (node (ref "U11F") (pin "L9") (pinfunction "DXN_0_L9") (pintype "passive"))
    )
    (net (code "197") (name "unconnected-(P11F-Pad19)") (class "Default")
      (node (ref "P11F") (pin "19") (pinfunction "19_19") (pintype "passive"))
    )
    (net (code "198") (name "unconnected-(P12F-Pad10)") (class "Default")
      (node (ref "P12F") (pin "10") (pinfunction "10_10") (pintype "passive"))
    )
    (net (code "199") (name "unconnected-(P12F-Pad15)") (class "Default")
      (node (ref "P12F") (pin "15") (pinfunction "15_15") (pintype "passive"))
    )
    (net (code "200") (name "unconnected-(U11FB-IO_25_14-PadR12)") (class "Default")
      (node (ref "U11F") (pin "R12") (pinfunction "IO_25_14_R12") (pintype "bidirectional"))
    )
    (net (code "201") (name "unconnected-(U11FB-IO_L6N_T0_D08_VREF_14-PadN13)") (class "Default")
      (node (ref "U11F") (pin "N13") (pinfunction "IO_L6N_T0_D08_VREF_14_N13") (pintype "bidirectional"))
    )
    (net (code "202") (name "unconnected-(U11FB-IO_L19P_T3_D26_14-PadP13)") (class "Default")
      (node (ref "U11F") (pin "P13") (pinfunction "IO_L19P_T3_D26_14_P13") (pintype "bidirectional"))
    )
    (net (code "203") (name "unconnected-(U11FB-IO_L22P_T3_D21_14-PadT12)") (class "Default")
      (node (ref "U11F") (pin "T12") (pinfunction "IO_L22P_T3_D21_14_T12") (pintype "bidirectional"))
    )
    (net (code "204") (name "unconnected-(U11FB-IO_L23N_T3_D18_14-PadT11)") (class "Default")
      (node (ref "U11F") (pin "T11") (pinfunction "IO_L23N_T3_D18_14_T11") (pintype "bidirectional"))
    )
    (net (code "205") (name "unconnected-(U11FB-IO_L23P_T3_D19_14-PadR11)") (class "Default")
      (node (ref "U11F") (pin "R11") (pinfunction "IO_L23P_T3_D19_14_R11") (pintype "bidirectional"))
    )
    (net (code "206") (name "unconnected-(U11FC-IO_25_15-PadK13)") (class "Default")
      (node (ref "U11F") (pin "K13") (pinfunction "IO_25_15_K13") (pintype "bidirectional"))
    )
    (net (code "207") (name "unconnected-(U11FC-IO_L16P_T2_15-PadF18)") (class "Default")
      (node (ref "U11F") (pin "F18") (pinfunction "IO_L16P_T2_15_F18") (pintype "bidirectional"))
    )
    (net (code "208") (name "unconnected-(U11FC-IO_L19N_T3_VREF_15-PadJ16)") (class "Default")
      (node (ref "U11F") (pin "J16") (pinfunction "IO_L19N_T3_VREF_15_J16") (pintype "bidirectional"))
    )
    (net (code "209") (name "unconnected-(U11FC-IO_L19P_T3_15-PadK16)") (class "Default")
      (node (ref "U11F") (pin "K16") (pinfunction "IO_L19P_T3_15_K16") (pintype "bidirectional"))
    )
    (net (code "210") (name "unconnected-(U11FC-IO_L20N_T3_15-PadH14)") (class "Default")
      (node (ref "U11F") (pin "H14") (pinfunction "IO_L20N_T3_15_H14") (pintype "bidirectional"))
    )
    (net (code "211") (name "unconnected-(U11FC-IO_L20P_T3_15-PadH13)") (class "Default")
      (node (ref "U11F") (pin "H13") (pinfunction "IO_L20P_T3_15_H13") (pintype "bidirectional"))
    )
    (net (code "212") (name "unconnected-(U11FC-IO_L21N_T3_DQS_15-PadG18)") (class "Default")
      (node (ref "U11F") (pin "G18") (pinfunction "IO_L21N_T3_DQS_15_G18") (pintype "bidirectional"))
    )
    (net (code "213") (name "unconnected-(U11FC-IO_L22P_T3_15-PadH16)") (class "Default")
      (node (ref "U11F") (pin "H16") (pinfunction "IO_L22P_T3_15_H16") (pintype "bidirectional"))
    )
    (net (code "214") (name "unconnected-(U11FC-IO_L23N_T3_15-PadJ15)") (class "Default")
      (node (ref "U11F") (pin "J15") (pinfunction "IO_L23N_T3_15_J15") (pintype "bidirectional"))
    )
    (net (code "215") (name "unconnected-(U11FC-IO_L23P_T3_15-PadK14)") (class "Default")
      (node (ref "U11F") (pin "K14") (pinfunction "IO_L23P_T3_15_K14") (pintype "bidirectional"))
    )
    (net (code "216") (name "unconnected-(U11FC-IO_L24N_T3_RS0_15-PadJ14)") (class "Default")
      (node (ref "U11F") (pin "J14") (pinfunction "IO_L24N_T3_RS0_15_J14") (pintype "bidirectional"))
    )
    (net (code "217") (name "unconnected-(U11FC-IO_L24P_T3_RS1_15-PadJ13)") (class "Default")
      (node (ref "U11F") (pin "J13") (pinfunction "IO_L24P_T3_RS1_15_J13") (pintype "bidirectional"))
    )
    (net (code "218") (name "unconnected-(U11FD-IO_L24P_T3_34-PadU7)") (class "Default")
      (node (ref "U11F") (pin "U7") (pinfunction "IO_L24P_T3_34_U7") (pintype "bidirectional"))
    )
    (net (code "219") (name "unconnected-(U11FF-IO_0_35-PadF6)") (class "Default")
      (node (ref "U11F") (pin "F6") (pinfunction "IO_0_35_F6") (pintype "bidirectional"))
    )
    (net (code "220") (name "unconnected-(U11FF-IO_25_35-PadJ5)") (class "Default")
      (node (ref "U11F") (pin "J5") (pinfunction "IO_25_35_J5") (pintype "bidirectional"))
    )
    (net (code "221") (name "unconnected-(U11FF-IO_L3N_T0_DQS_AD5N_35-PadC7)") (class "Default")
      (node (ref "U11F") (pin "C7") (pinfunction "IO_L3N_T0_DQS_AD5N_35_C7") (pintype "bidirectional"))
    )
    (net (code "222") (name "unconnected-(U11FF-IO_L3P_T0_DQS_AD5P_35-PadD7)") (class "Default")
      (node (ref "U11F") (pin "D7") (pinfunction "IO_L3P_T0_DQS_AD5P_35_D7") (pintype "bidirectional"))
    )
    (net (code "223") (name "unconnected-(U11FF-IO_L4N_T0_35-PadA6)") (class "Default")
      (node (ref "U11F") (pin "A6") (pinfunction "IO_L4N_T0_35_A6") (pintype "bidirectional"))
    )
    (net (code "224") (name "unconnected-(U11FF-IO_L5N_T0_AD13N_35-PadD6)") (class "Default")
      (node (ref "U11F") (pin "D6") (pinfunction "IO_L5N_T0_AD13N_35_D6") (pintype "bidirectional"))
    )
    (net (code "225") (name "unconnected-(U11FF-IO_L5P_T0_AD13P_35-PadE6)") (class "Default")
      (node (ref "U11F") (pin "E6") (pinfunction "IO_L5P_T0_AD13P_35_E6") (pintype "bidirectional"))
    )
    (net (code "226") (name "unconnected-(U11FF-IO_L6N_T0_VREF_35-PadD5)") (class "Default")
      (node (ref "U11F") (pin "D5") (pinfunction "IO_L6N_T0_VREF_35_D5") (pintype "bidirectional"))
    )
    (net (code "227") (name "unconnected-(U11FF-IO_L6P_T0_35-PadE5)") (class "Default")
      (node (ref "U11F") (pin "E5") (pinfunction "IO_L6P_T0_35_E5") (pintype "bidirectional"))
    )
    (net (code "228") (name "unconnected-(U11FF-IO_L13N_T2_MRCC_35-PadE4)") (class "Default")
      (node (ref "U11F") (pin "E4") (pinfunction "IO_L13N_T2_MRCC_35_E4") (pintype "bidirectional"))
    )
    (net (code "229") (name "unconnected-(U11FF-IO_L13P_T2_MRCC_35-PadF4)") (class "Default")
      (node (ref "U11F") (pin "F4") (pinfunction "IO_L13P_T2_MRCC_35_F4") (pintype "bidirectional"))
    )
    (net (code "230") (name "unconnected-(U11FF-IO_L14P_T2_SRCC_35-PadE1)") (class "Default")
      (node (ref "U11F") (pin "E1") (pinfunction "IO_L14P_T2_SRCC_35_E1") (pintype "bidirectional"))
    )
    (net (code "231") (name "unconnected-(U11FF-IO_L15N_T2_DQS_35-PadE3)") (class "Default")
      (node (ref "U11F") (pin "E3") (pinfunction "IO_L15N_T2_DQS_35_E3") (pintype "bidirectional"))
    )
    (net (code "232") (name "unconnected-(U11FF-IO_L15P_T2_DQS_35-PadF3)") (class "Default")
      (node (ref "U11F") (pin "F3") (pinfunction "IO_L15P_T2_DQS_35_F3") (pintype "bidirectional"))
    )
    (net (code "233") (name "unconnected-(U11FF-IO_L16N_T2_35-PadD2)") (class "Default")
      (node (ref "U11F") (pin "D2") (pinfunction "IO_L16N_T2_35_D2") (pintype "bidirectional"))
    )
    (net (code "234") (name "unconnected-(U11FF-IO_L16P_T2_35-PadE2)") (class "Default")
      (node (ref "U11F") (pin "E2") (pinfunction "IO_L16P_T2_35_E2") (pintype "bidirectional"))
    )
    (net (code "235") (name "unconnected-(U11FF-IO_L17N_T2_35-PadF5)") (class "Default")
      (node (ref "U11F") (pin "F5") (pinfunction "IO_L17N_T2_35_F5") (pintype "bidirectional"))
    )
    (net (code "236") (name "unconnected-(U11FF-IO_L17P_T2_35-PadG5)") (class "Default")
      (node (ref "U11F") (pin "G5") (pinfunction "IO_L17P_T2_35_G5") (pintype "bidirectional"))
    )
    (net (code "237") (name "unconnected-(U11FF-IO_L18N_T2_35-PadF1)") (class "Default")
      (node (ref "U11F") (pin "F1") (pinfunction "IO_L18N_T2_35_F1") (pintype "bidirectional"))
    )
    (net (code "238") (name "unconnected-(U11FF-IO_L19N_T3_VREF_35-PadJ3)") (class "Default")
      (node (ref "U11F") (pin "J3") (pinfunction "IO_L19N_T3_VREF_35_J3") (pintype "bidirectional"))
    )
    (net (code "239") (name "unconnected-(U11FF-IO_L19P_T3_35-PadJ4)") (class "Default")
      (node (ref "U11F") (pin "J4") (pinfunction "IO_L19P_T3_35_J4") (pintype "bidirectional"))
    )
    (net (code "240") (name "unconnected-(U11FF-IO_L20N_T3_35-PadH2)") (class "Default")
      (node (ref "U11F") (pin "H2") (pinfunction "IO_L20N_T3_35_H2") (pintype "bidirectional"))
    )
    (net (code "241") (name "unconnected-(U11FF-IO_L20P_T3_35-PadH3)") (class "Default")
      (node (ref "U11F") (pin "H3") (pinfunction "IO_L20P_T3_35_H3") (pintype "bidirectional"))
    )
    (net (code "242") (name "unconnected-(U11FF-IO_L21N_T3_DQS_35-PadG1)") (class "Default")
      (node (ref "U11F") (pin "G1") (pinfunction "IO_L21N_T3_DQS_35_G1") (pintype "bidirectional"))
    )
    (net (code "243") (name "unconnected-(U11FF-IO_L22N_T3_35-PadH4)") (class "Default")
      (node (ref "U11F") (pin "H4") (pinfunction "IO_L22N_T3_35_H4") (pintype "bidirectional"))
    )
    (net (code "244") (name "unconnected-(U11FF-IO_L22P_T3_35-PadH5)") (class "Default")
      (node (ref "U11F") (pin "H5") (pinfunction "IO_L22P_T3_35_H5") (pintype "bidirectional"))
    )
    (net (code "245") (name "unconnected-(U11FF-IO_L23N_T3_35-PadJ1)") (class "Default")
      (node (ref "U11F") (pin "J1") (pinfunction "IO_L23N_T3_35_J1") (pintype "bidirectional"))
    )
    (net (code "246") (name "unconnected-(U11FF-IO_L23P_T3_35-PadJ2)") (class "Default")
      (node (ref "U11F") (pin "J2") (pinfunction "IO_L23P_T3_35_J2") (pintype "bidirectional"))
    )
    (net (code "247") (name "unconnected-(U11FF-IO_L24N_T3_35-PadG6)") (class "Default")
      (node (ref "U11F") (pin "G6") (pinfunction "IO_L24N_T3_35_G6") (pintype "bidirectional"))
    )
    (net (code "248") (name "unconnected-(U11FF-IO_L24P_T3_35-PadH6)") (class "Default")
      (node (ref "U11F") (pin "H6") (pinfunction "IO_L24P_T3_35_H6") (pintype "bidirectional"))
    )
    (net (code "249") (name "unconnected-(U11FG-IO_L6N_T0_VREF_16-PadD11)") (class "Default")
      (node (ref "U11F") (pin "D11") (pinfunction "IO_L6N_T0_VREF_16_D11") (pintype "bidirectional"))
    )
    (net (code "250") (name "unconnected-(U11FG-IO_L11N_T1_SRCC_16-PadC9)") (class "Default")
      (node (ref "U11F") (pin "C9") (pinfunction "IO_L11N_T1_SRCC_16_C9") (pintype "bidirectional"))
    )
    (net (code "251") (name "unconnected-(U11FG-IO_L11P_T1_SRCC_16-PadC10)") (class "Default")
      (node (ref "U11F") (pin "C10") (pinfunction "IO_L11P_T1_SRCC_16_C10") (pintype "bidirectional"))
    )
    (net (code "252") (name "unconnected-(U11FG-IO_L12N_T1_MRCC_16-PadA9)") (class "Default")
      (node (ref "U11F") (pin "A9") (pinfunction "IO_L12N_T1_MRCC_16_A9") (pintype "bidirectional"))
    )
    (net (code "253") (name "unconnected-(U11FG-IO_L12P_T1_MRCC_16-PadA10)") (class "Default")
      (node (ref "U11F") (pin "A10") (pinfunction "IO_L12P_T1_MRCC_16_A10") (pintype "bidirectional"))
    )
    (net (code "254") (name "unconnected-(U11FG-IO_L13N_T2_MRCC_16-PadC11)") (class "Default")
      (node (ref "U11F") (pin "C11") (pinfunction "IO_L13N_T2_MRCC_16_C11") (pintype "bidirectional"))
    )
    (net (code "255") (name "unconnected-(U11FG-IO_L14N_T2_SRCC_16-PadA11)") (class "Default")
      (node (ref "U11F") (pin "A11") (pinfunction "IO_L14N_T2_SRCC_16_A11") (pintype "bidirectional"))
    )
    (net (code "256") (name "unconnected-(U11FG-IO_L14P_T2_SRCC_16-PadB11)") (class "Default")
      (node (ref "U11F") (pin "B11") (pinfunction "IO_L14P_T2_SRCC_16_B11") (pintype "bidirectional"))
    )
    (net (code "257") (name "unconnected-(U11FG-IO_L19N_T3_VREF_16-PadD10)") (class "Default")
      (node (ref "U11F") (pin "D10") (pinfunction "IO_L19N_T3_VREF_16_D10") (pintype "bidirectional"))
    )
    (net (code "258") (name "unconnected-(U18F-CLKOUT-Pad5)") (class "Default")
      (node (ref "U18F") (pin "5") (pinfunction "CLKOUT_5") (pintype "open_collector"))
    )
  )
)
